# Data_Logger_V3_1.net
KiCad netlist of a schematic drawn in EAGLE
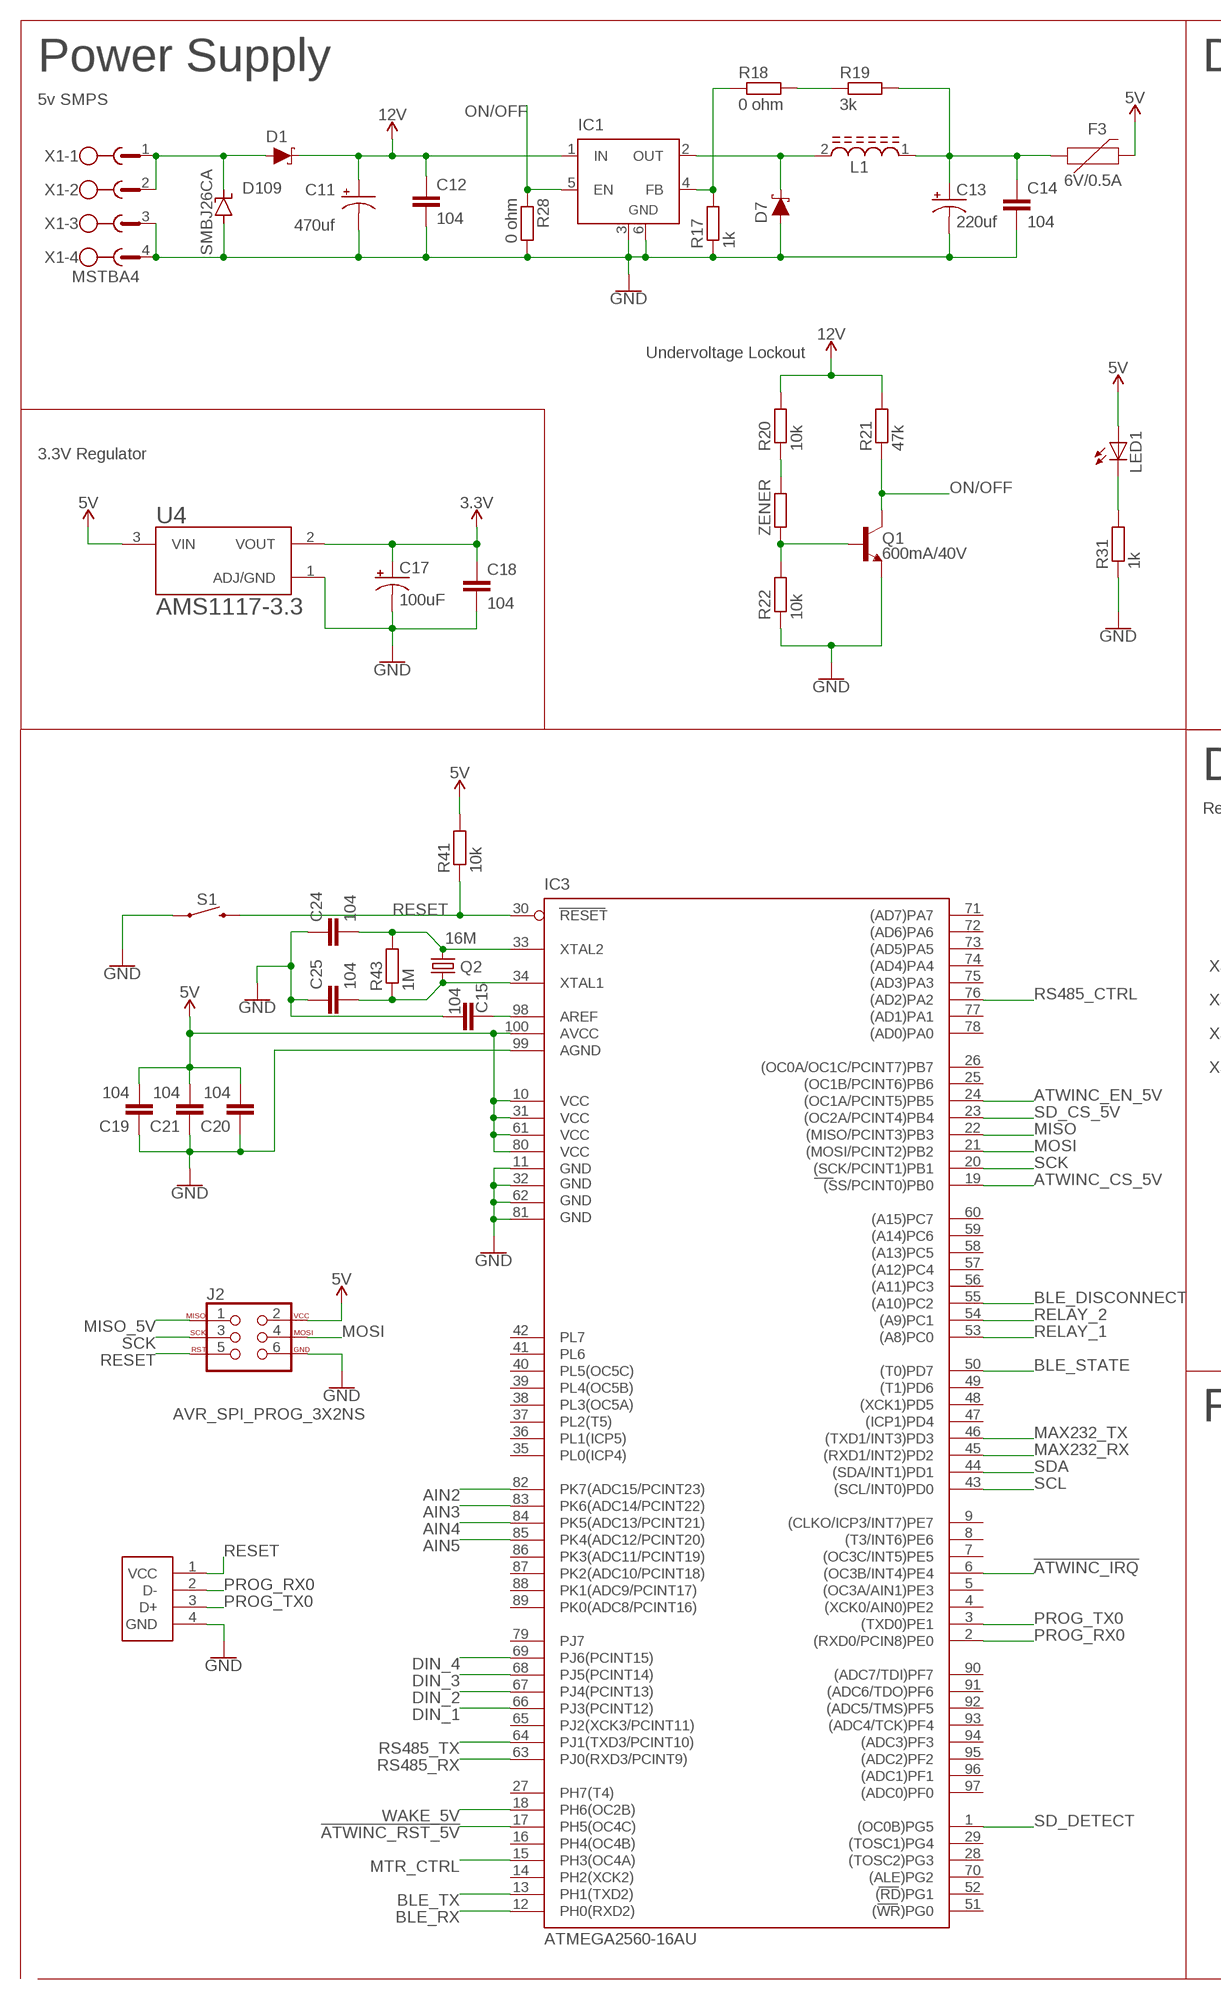
[diagram p0: schematic, sheet 1, part 1 of 3]
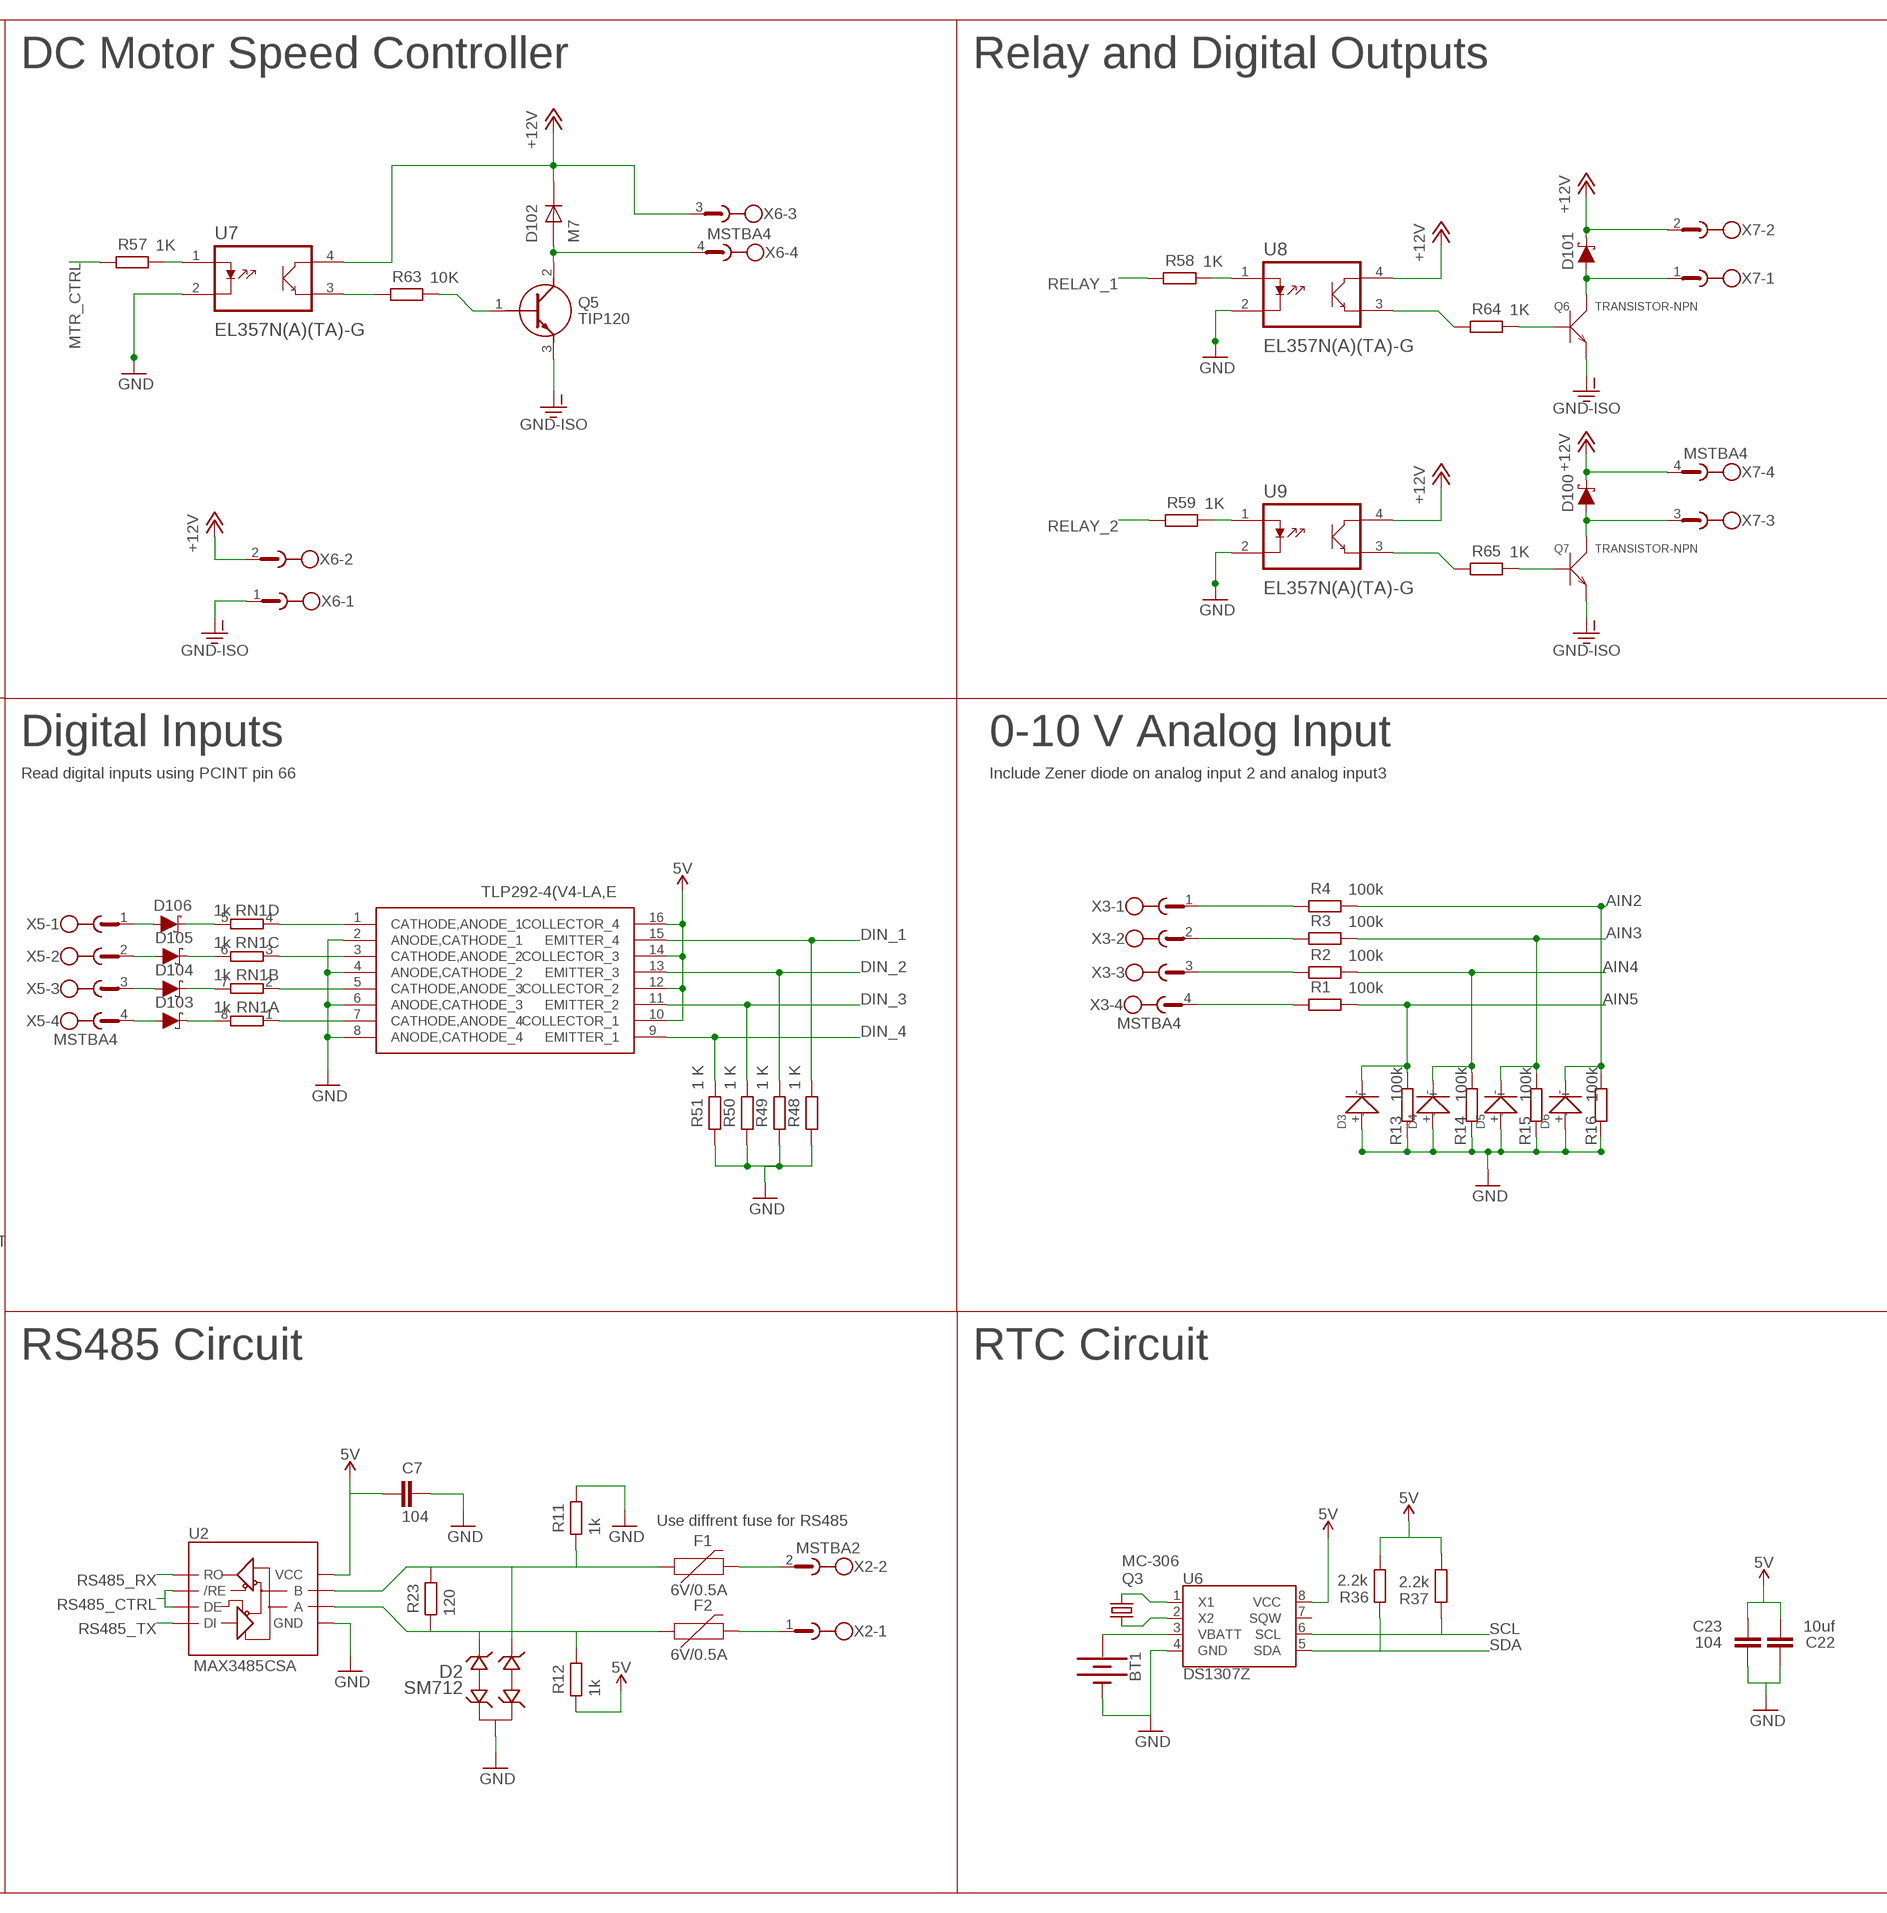
[diagram p1: schematic, sheet 1, part 2 of 3]
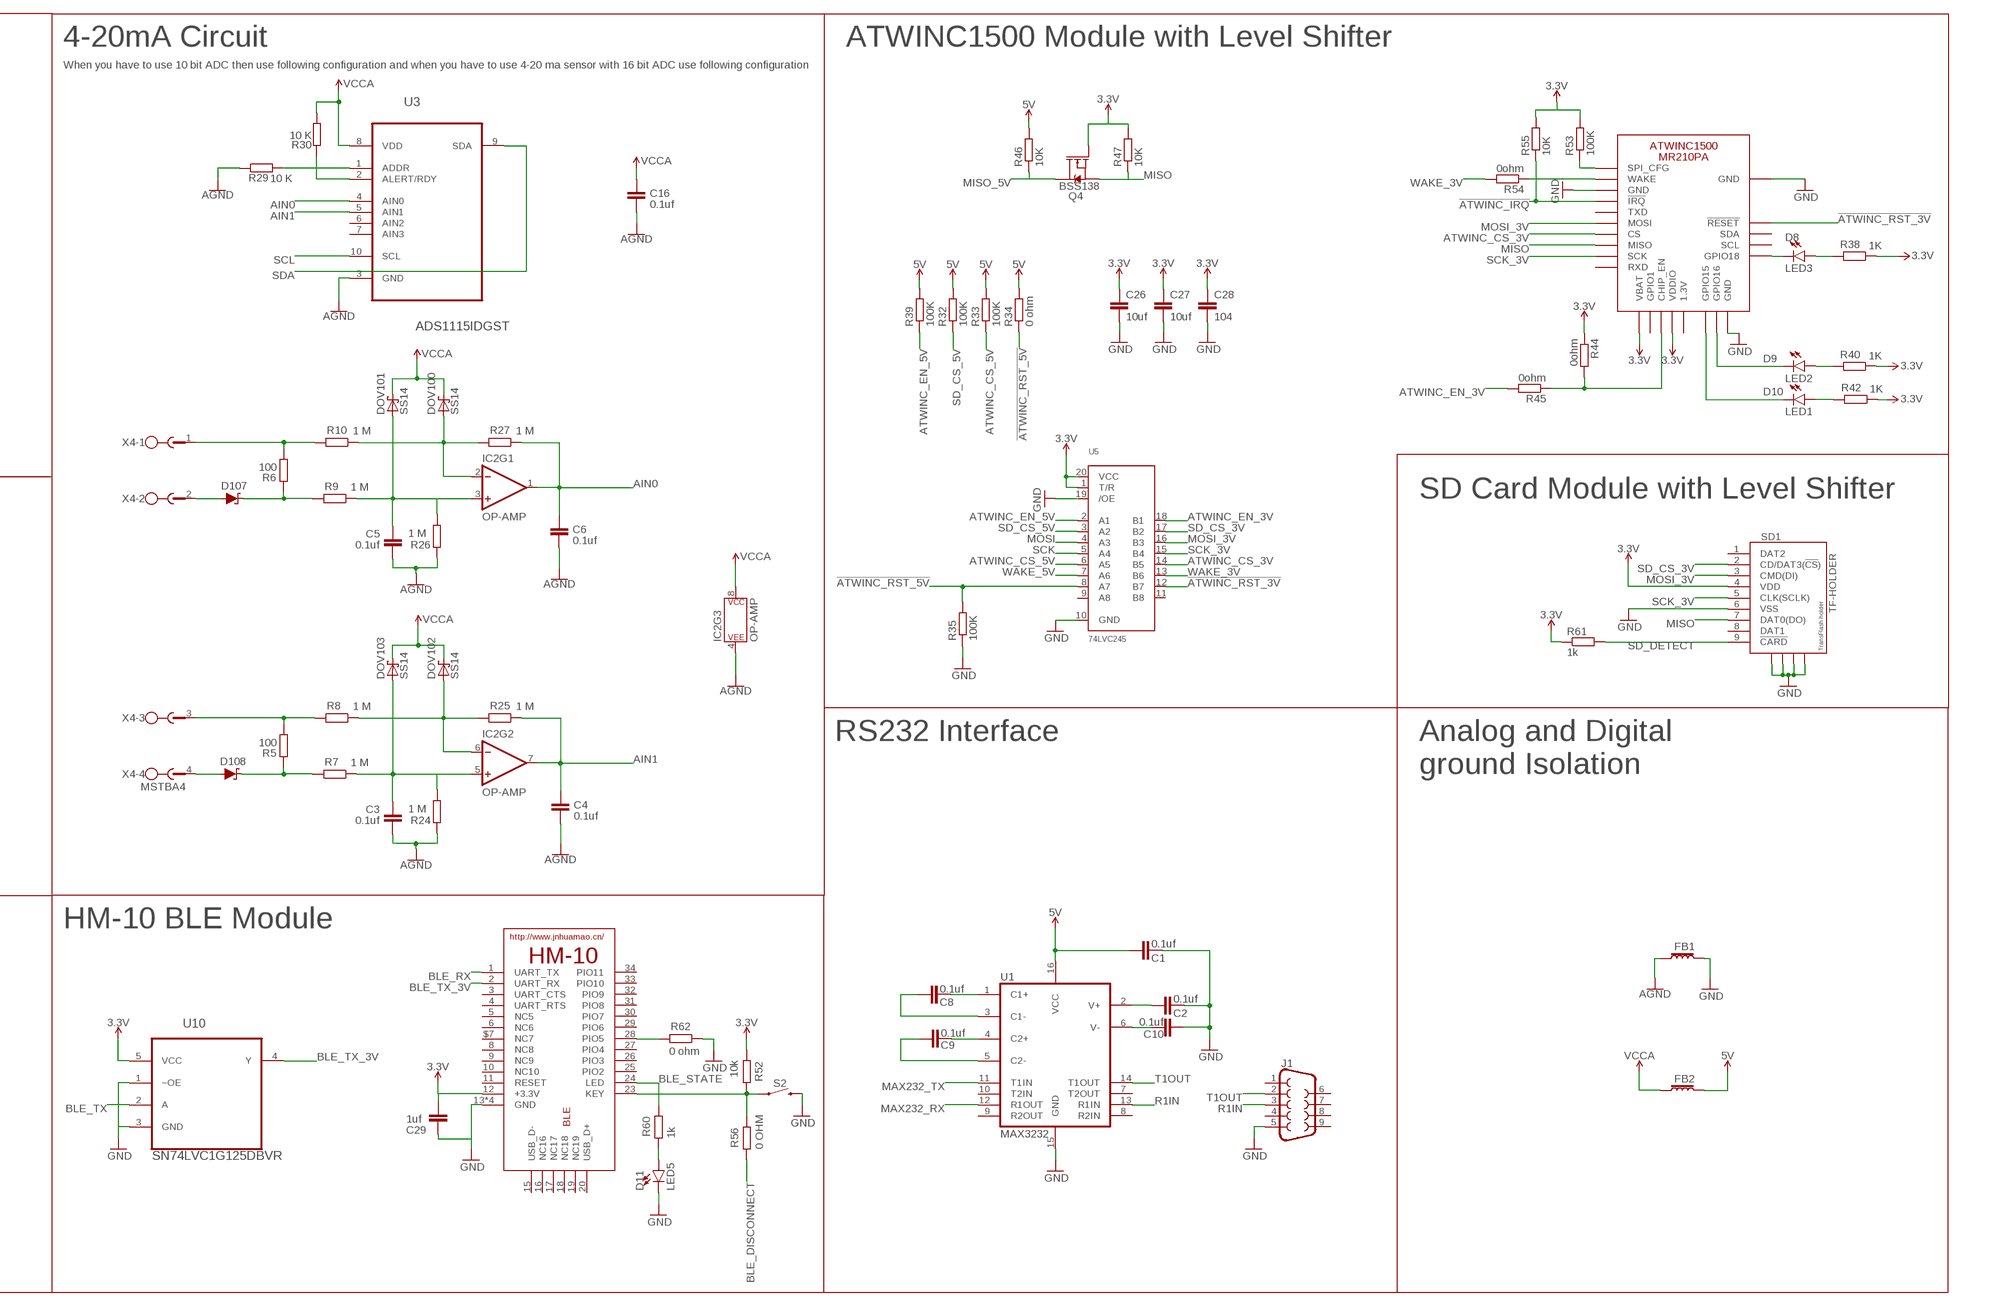
[diagram p2: schematic, sheet 1, part 3 of 3]

(export (version "E")
  (design (tool "Eeschema 10.0.6"))
  (components
    (comp (ref "BLE")
      (value "HM-10-BOARD")
      (footprint "eagle-import:26.9X13X2.2_BOARD")
      (libsource (lib "eagle-import") (part "HM-10-BOARD"))
    )
    (comp (ref "BT1")
      (value "BATTERY-20MM_PTH")
      (footprint "eagle-import:BATTCOM_20MM_PTH")
      (libsource (lib "eagle-import") (part "BATTERY-20MM_PTH"))
    )
    (comp (ref "C1")
      (value "0.1uf")
      (footprint "eagle-import:C0805")
      (libsource (lib "eagle-import") (part "C-EUC0805"))
    )
    (comp (ref "C2")
      (value "0.1uf")
      (footprint "eagle-import:C0805")
      (libsource (lib "eagle-import") (part "C-EUC0805"))
    )
    (comp (ref "C3")
      (value "0.1uf")
      (footprint "eagle-import:C0805")
      (libsource (lib "eagle-import") (part "C-EUC0805"))
    )
    (comp (ref "C4")
      (value "0.1uf")
      (footprint "eagle-import:C0805")
      (libsource (lib "eagle-import") (part "C-EUC0805"))
    )
    (comp (ref "C5")
      (value "0.1uf")
      (footprint "eagle-import:C0805")
      (libsource (lib "eagle-import") (part "C-EUC0805"))
    )
    (comp (ref "C6")
      (value "0.1uf")
      (footprint "eagle-import:C0805")
      (libsource (lib "eagle-import") (part "C-EUC0805"))
    )
    (comp (ref "C7")
      (value "104")
      (footprint "eagle-import:C0805")
      (libsource (lib "eagle-import") (part "C-EUC0805"))
    )
    (comp (ref "C8")
      (value "0.1uf")
      (footprint "eagle-import:C0805")
      (libsource (lib "eagle-import") (part "C-EUC0805"))
    )
    (comp (ref "C9")
      (value "0.1uf")
      (footprint "eagle-import:C0805")
      (libsource (lib "eagle-import") (part "C-EUC0805"))
    )
    (comp (ref "C10")
      (value "0.1uf")
      (footprint "eagle-import:C0805")
      (libsource (lib "eagle-import") (part "C-EUC0805"))
    )
    (comp (ref "C11")
      (value "470uf")
      (footprint "eagle-import:E5-8,5")
      (libsource (lib "eagle-import") (part "CPOL-USE5-8.5"))
    )
    (comp (ref "C12")
      (value "104")
      (footprint "eagle-import:C0805")
      (libsource (lib "eagle-import") (part "C-EUC0805"))
    )
    (comp (ref "C13")
      (value "220uf")
      (footprint "eagle-import:150CLZ-1014")
      (libsource (lib "eagle-import") (part "CPOL-US150CLZ-1014"))
    )
    (comp (ref "C14")
      (value "104")
      (footprint "eagle-import:C0805")
      (libsource (lib "eagle-import") (part "C-EUC0805"))
    )
    (comp (ref "C15")
      (value "104")
      (footprint "eagle-import:C0805")
      (libsource (lib "eagle-import") (part "C-EUC0805"))
    )
    (comp (ref "C16")
      (value "0.1uf")
      (footprint "eagle-import:C0805")
      (libsource (lib "eagle-import") (part "C-EUC0805"))
    )
    (comp (ref "C17")
      (value "100uF")
      (footprint "eagle-import:PANASONIC_D")
      (libsource (lib "eagle-import") (part "100UF-POLAR-25V-20%(ELEC)"))
    )
    (comp (ref "C18")
      (value "104")
      (footprint "eagle-import:C0805")
      (libsource (lib "eagle-import") (part "C-EUC0805"))
    )
    (comp (ref "C19")
      (value "104")
      (footprint "eagle-import:C0805")
      (libsource (lib "eagle-import") (part "C-EUC0805"))
    )
    (comp (ref "C20")
      (value "104")
      (footprint "eagle-import:C0805")
      (libsource (lib "eagle-import") (part "C-EUC0805"))
    )
    (comp (ref "C21")
      (value "104")
      (footprint "eagle-import:C0805")
      (libsource (lib "eagle-import") (part "C-EUC0805"))
    )
    (comp (ref "C22")
      (value "10uf")
      (footprint "eagle-import:C0805")
      (libsource (lib "eagle-import") (part "C-EUC0805"))
    )
    (comp (ref "C23")
      (value "104")
      (footprint "eagle-import:C0805")
      (libsource (lib "eagle-import") (part "C-EUC0805"))
    )
    (comp (ref "C24")
      (value "104")
      (footprint "eagle-import:C0805")
      (libsource (lib "eagle-import") (part "C-EUC0805"))
    )
    (comp (ref "C25")
      (value "104")
      (footprint "eagle-import:C0805")
      (libsource (lib "eagle-import") (part "C-EUC0805"))
    )
    (comp (ref "C26")
      (value "10uf")
      (footprint "eagle-import:C0805")
      (libsource (lib "eagle-import") (part "C-EUC0805"))
    )
    (comp (ref "C27")
      (value "10uf")
      (footprint "eagle-import:C0805")
      (libsource (lib "eagle-import") (part "C-EUC0805"))
    )
    (comp (ref "C28")
      (value "104")
      (footprint "eagle-import:C0805")
      (libsource (lib "eagle-import") (part "C-EUC0805"))
    )
    (comp (ref "C29")
      (value "1uf")
      (footprint "eagle-import:C0805")
      (libsource (lib "eagle-import") (part "C-EUC0805"))
    )
    (comp (ref "D1")
      (value "3A/40V/500mV")
      (footprint "eagle-import:SMA-DIODE")
      (libsource (lib "eagle-import") (part "DIODE-SCHOTTKY-B340A"))
    )
    (comp (ref "D2")
      (value "SM712")
      (footprint "eagle-import:SOT-23-3")
      (fields (field (name "MF") "Bourns") (field (name "MP") "CDSOT23-SM712"))
      (libsource (lib "eagle-import") (part "CDSOT23-SM712"))
    )
    (comp (ref "D3")
      (value "SMD-DIODE-ZENER-5.1V-500MW(SOD-123)")
      (footprint "eagle-import:SOD-123")
      (fields (field (name "MF") "Vishay") (field (name "MP") "MMSZ4689-V-GS08"))
      (libsource (lib "eagle-import") (part "SMD-DIODE-ZENER-5.1V-500MW(SOD-123)"))
    )
    (comp (ref "D4")
      (value "SMD-DIODE-ZENER-5.1V-500MW(SOD-123)")
      (footprint "eagle-import:SOD-123")
      (fields (field (name "MF") "Vishay") (field (name "MP") "MMSZ4689-V-GS08"))
      (libsource (lib "eagle-import") (part "SMD-DIODE-ZENER-5.1V-500MW(SOD-123)"))
    )
    (comp (ref "D5")
      (value "SMD-DIODE-ZENER-5.1V-500MW(SOD-123)")
      (footprint "eagle-import:SOD-123")
      (fields (field (name "MF") "Vishay") (field (name "MP") "MMSZ4689-V-GS08"))
      (libsource (lib "eagle-import") (part "SMD-DIODE-ZENER-5.1V-500MW(SOD-123)"))
    )
    (comp (ref "D6")
      (value "SMD-DIODE-ZENER-5.1V-500MW(SOD-123)")
      (footprint "eagle-import:SOD-123")
      (fields (field (name "MF") "Vishay") (field (name "MP") "MMSZ4689-V-GS08"))
      (libsource (lib "eagle-import") (part "SMD-DIODE-ZENER-5.1V-500MW(SOD-123)"))
    )
    (comp (ref "D7")
      (value "3A/40V/500mV")
      (footprint "eagle-import:SMA-DIODE")
      (libsource (lib "eagle-import") (part "DIODE-SCHOTTKY-B340A"))
    )
    (comp (ref "D8")
      (value "LED3")
      (footprint "eagle-import:LED-0603")
      (libsource (lib "eagle-import") (part "LED-RED0603-SMART"))
    )
    (comp (ref "D9")
      (value "LED2")
      (footprint "eagle-import:LED-0603")
      (libsource (lib "eagle-import") (part "LED-GREEN0603"))
    )
    (comp (ref "D10")
      (value "LED1")
      (footprint "eagle-import:LED-0603")
      (libsource (lib "eagle-import") (part "LED-GREEN0603"))
    )
    (comp (ref "D11")
      (value "LED5")
      (footprint "eagle-import:LED-0603")
      (libsource (lib "eagle-import") (part "LED-GREEN0603"))
    )
    (comp (ref "D100")
      (value "3A/40V/500mV")
      (footprint "eagle-import:SMA-DIODE")
      (libsource (lib "eagle-import") (part "DIODE-SCHOTTKY-B340A"))
    )
    (comp (ref "D101")
      (value "3A/40V/500mV")
      (footprint "eagle-import:SMA-DIODE")
      (libsource (lib "eagle-import") (part "DIODE-SCHOTTKY-B340A"))
    )
    (comp (ref "D102")
      (value "M7")
      (footprint "eagle-import:DIOM505270X240")
      (fields (field (name "MF") "Diodes Inc."))
      (libsource (lib "eagle-import") (part "M7"))
    )
    (comp (ref "D103")
      (value "3A/40V/500mV")
      (footprint "eagle-import:SMA-DIODE")
      (libsource (lib "eagle-import") (part "DIODE-SCHOTTKY-B340A"))
    )
    (comp (ref "D104")
      (value "3A/40V/500mV")
      (footprint "eagle-import:SMA-DIODE")
      (libsource (lib "eagle-import") (part "DIODE-SCHOTTKY-B340A"))
    )
    (comp (ref "D105")
      (value "3A/40V/500mV")
      (footprint "eagle-import:SMA-DIODE")
      (libsource (lib "eagle-import") (part "DIODE-SCHOTTKY-B340A"))
    )
    (comp (ref "D106")
      (value "3A/40V/500mV")
      (footprint "eagle-import:SMA-DIODE")
      (libsource (lib "eagle-import") (part "DIODE-SCHOTTKY-B340A"))
    )
    (comp (ref "D107")
      (value "3A/40V/500mV")
      (footprint "eagle-import:SMA-DIODE")
      (libsource (lib "eagle-import") (part "DIODE-SCHOTTKY-B340A"))
    )
    (comp (ref "D108")
      (value "3A/40V/500mV")
      (footprint "eagle-import:SMA-DIODE")
      (libsource (lib "eagle-import") (part "DIODE-SCHOTTKY-B340A"))
    )
    (comp (ref "D109")
      (value "SMBJ26CA")
      (footprint "eagle-import:SMBJ")
      (libsource (lib "eagle-import") (part "SUPPRESSOR-SMBJ"))
    )
    (comp (ref "DOV100")
      (value "SS14")
      (footprint "eagle-import:DO-214AC")
      (fields (field (name "MF") "ON Semiconductor"))
      (libsource (lib "eagle-import") (part "SS14"))
    )
    (comp (ref "DOV101")
      (value "SS14")
      (footprint "eagle-import:DO-214AC")
      (fields (field (name "MF") "ON Semiconductor"))
      (libsource (lib "eagle-import") (part "SS14"))
    )
    (comp (ref "DOV102")
      (value "SS14")
      (footprint "eagle-import:DO-214AC")
      (fields (field (name "MF") "ON Semiconductor"))
      (libsource (lib "eagle-import") (part "SS14"))
    )
    (comp (ref "DOV103")
      (value "SS14")
      (footprint "eagle-import:DO-214AC")
      (fields (field (name "MF") "ON Semiconductor"))
      (libsource (lib "eagle-import") (part "SS14"))
    )
    (comp (ref "F1")
      (value "6V/0.5A")
      (footprint "eagle-import:1206")
      (libsource (lib "eagle-import") (part "PPTC_HALF-AMP"))
    )
    (comp (ref "F2")
      (value "6V/0.5A")
      (footprint "eagle-import:1206")
      (libsource (lib "eagle-import") (part "PPTC_HALF-AMP"))
    )
    (comp (ref "F3")
      (value "6V/0.5A")
      (footprint "eagle-import:1206")
      (libsource (lib "eagle-import") (part "PPTC_HALF-AMP"))
    )
    (comp (ref "FB1")
      (value "30Ω/1.8A")
      (footprint "eagle-import:0603")
      (libsource (lib "eagle-import") (part "FERRITE_BEAD-0603"))
    )
    (comp (ref "FB2")
      (value "30Ω/1.8A")
      (footprint "eagle-import:0603")
      (libsource (lib "eagle-import") (part "FERRITE_BEAD-0603"))
    )
    (comp (ref "IC1")
      (value "LM2596S")
      (footprint "eagle-import:TO263-5")
      (libsource (lib "eagle-import") (part "LM2596S"))
    )
    (comp (ref "IC2")
      (value "OP-AMP")
      (footprint "eagle-import:SO08")
      (libsource (lib "eagle-import") (part "OPAMP-DUALU"))
    )
    (comp (ref "IC3")
      (value "ATMEGA2560-16AU")
      (footprint "eagle-import:TQFP100")
      (libsource (lib "eagle-import") (part "ATMEGA2560AU2560-16"))
    )
    (comp (ref "IC4")
      (value "TLP292-4(V4-LA,E")
      (footprint "eagle-import:SOIC127P700X230-16N")
      (fields (field (name "MOUSER_PART_NUMBER") "757-TLP292-4V4-LAE"))
      (libsource (lib "eagle-import") (part "TLP292-4(V4-LA,E"))
    )
    (comp (ref "J1")
      (value "DB9MALE")
      (footprint "eagle-import:DB9_MALE")
      (libsource (lib "eagle-import") (part "DB9MALE"))
    )
    (comp (ref "J2")
      (value "AVR_SPI_PROG_3X2NS")
      (footprint "eagle-import:2X3-NS")
      (libsource (lib "eagle-import") (part "AVR_SPI_PROG_3X2NS"))
    )
    (comp (ref "L1")
      (value "SRR1260-680M")
      (footprint "eagle-import:INDP125125X600N")
      (fields (field (name "MF") "Bourns - J.W. Miller"))
      (libsource (lib "eagle-import") (part "SRR1260-680M"))
    )
    (comp (ref "LED1")
      (value "LEDCHIP-LED0805")
      (footprint "eagle-import:CHIP-LED0805")
      (libsource (lib "eagle-import") (part "LEDCHIP-LED0805"))
    )
    (comp (ref "PROG")
      (value "61400416121")
      (footprint "eagle-import:61400416121")
      (libsource (lib "eagle-import") (part "61400416121"))
    )
    (comp (ref "Q1")
      (value "600mA/40V")
      (footprint "eagle-import:SOT23-3")
      (libsource (lib "eagle-import") (part "TRANS_NPN-MMBT2222AL"))
    )
    (comp (ref "Q2")
      (value "16M")
      (footprint "eagle-import:HC49US")
      (libsource (lib "eagle-import") (part "CRYSTALHC49US"))
    )
    (comp (ref "Q3")
      (value "MC-306")
      (footprint "eagle-import:MC-306")
      (fields (field (name "MPN") "MC-306 60.0KHZ  100PPM ,12.5PF"))
      (libsource (lib "eagle-import") (part "MC-306"))
    )
    (comp (ref "Q4")
      (value "BSS138")
      (footprint "eagle-import:SOT23-3")
      (libsource (lib "eagle-import") (part "MOSFET-NCH-AO3404A"))
    )
    (comp (ref "Q5")
      (value "TIP120")
      (footprint "eagle-import:TO220")
      (fields (field (name "MOUSER_PART_NUMBER") "512-TIP120"))
      (libsource (lib "eagle-import") (part "TIP120"))
    )
    (comp (ref "Q6")
      (value "TRANSISTOR-NPN")
      (footprint "eagle-import:SOT-23")
      (fields (field (name "MF") "STMicroelectronics") (field (name "MP") "BC817-40"))
      (libsource (lib "eagle-import") (part "TRANSISTOR-NPN"))
    )
    (comp (ref "Q7")
      (value "TRANSISTOR-NPN")
      (footprint "eagle-import:SOT-23")
      (fields (field (name "MF") "STMicroelectronics") (field (name "MP") "BC817-40"))
      (libsource (lib "eagle-import") (part "TRANSISTOR-NPN"))
    )
    (comp (ref "R1")
      (value "100k")
      (footprint "eagle-import:R0805")
      (libsource (lib "eagle-import") (part "resistor_348_R-EU_R0805"))
    )
    (comp (ref "R2")
      (value "100k")
      (footprint "eagle-import:R0805")
      (libsource (lib "eagle-import") (part "resistor_348_R-EU_R0805"))
    )
    (comp (ref "R3")
      (value "100k")
      (footprint "eagle-import:R0805")
      (libsource (lib "eagle-import") (part "resistor_348_R-EU_R0805"))
    )
    (comp (ref "R4")
      (value "100k")
      (footprint "eagle-import:R0805")
      (libsource (lib "eagle-import") (part "resistor_348_R-EU_R0805"))
    )
    (comp (ref "R5")
      (value "100")
      (footprint "eagle-import:R0805")
      (libsource (lib "eagle-import") (part "resistor_348_R-EU_R0805"))
    )
    (comp (ref "R6")
      (value "100")
      (footprint "eagle-import:R0805")
      (libsource (lib "eagle-import") (part "resistor_348_R-EU_R0805"))
    )
    (comp (ref "R7")
      (value "1 M")
      (footprint "eagle-import:R0805")
      (libsource (lib "eagle-import") (part "resistor_348_R-EU_R0805"))
    )
    (comp (ref "R8")
      (value "1 M")
      (footprint "eagle-import:R0805")
      (libsource (lib "eagle-import") (part "resistor_348_R-EU_R0805"))
    )
    (comp (ref "R9")
      (value "1 M")
      (footprint "eagle-import:R0805")
      (libsource (lib "eagle-import") (part "resistor_348_R-EU_R0805"))
    )
    (comp (ref "R10")
      (value "1 M")
      (footprint "eagle-import:R0805")
      (libsource (lib "eagle-import") (part "resistor_348_R-EU_R0805"))
    )
    (comp (ref "R11")
      (value "1k")
      (footprint "eagle-import:R0805")
      (libsource (lib "eagle-import") (part "resistor_348_R-EU_R0805"))
    )
    (comp (ref "R12")
      (value "1k")
      (footprint "eagle-import:R0805")
      (libsource (lib "eagle-import") (part "resistor_348_R-EU_R0805"))
    )
    (comp (ref "R13")
      (value "100k")
      (footprint "eagle-import:R0805")
      (libsource (lib "eagle-import") (part "resistor_348_R-EU_R0805"))
    )
    (comp (ref "R14")
      (value "100k")
      (footprint "eagle-import:R0805")
      (libsource (lib "eagle-import") (part "resistor_348_R-EU_R0805"))
    )
    (comp (ref "R15")
      (value "100k")
      (footprint "eagle-import:R0805")
      (libsource (lib "eagle-import") (part "resistor_348_R-EU_R0805"))
    )
    (comp (ref "R16")
      (value "100k")
      (footprint "eagle-import:R0805")
      (libsource (lib "eagle-import") (part "resistor_348_R-EU_R0805"))
    )
    (comp (ref "R17")
      (value "1k")
      (footprint "eagle-import:R0805")
      (libsource (lib "eagle-import") (part "R-EU_R0805"))
    )
    (comp (ref "R18")
      (value "0 ohm")
      (footprint "eagle-import:R0805")
      (libsource (lib "eagle-import") (part "R-EU_R0805"))
    )
    (comp (ref "R19")
      (value "3k")
      (footprint "eagle-import:R0805")
      (libsource (lib "eagle-import") (part "R-EU_R0805"))
    )
    (comp (ref "R20")
      (value "10k")
      (footprint "eagle-import:R0805")
      (libsource (lib "eagle-import") (part "R-EU_R0805"))
    )
    (comp (ref "R21")
      (value "47k")
      (footprint "eagle-import:R0805")
      (libsource (lib "eagle-import") (part "R-EU_R0805"))
    )
    (comp (ref "R22")
      (value "10k")
      (footprint "eagle-import:R0805")
      (libsource (lib "eagle-import") (part "R-EU_R0805"))
    )
    (comp (ref "R23")
      (value "120")
      (footprint "eagle-import:R0805")
      (libsource (lib "eagle-import") (part "resistor_348_R-EU_R0805"))
    )
    (comp (ref "R24")
      (value "1 M")
      (footprint "eagle-import:R0805")
      (libsource (lib "eagle-import") (part "resistor_348_R-EU_R0805"))
    )
    (comp (ref "R25")
      (value "1 M")
      (footprint "eagle-import:R0805")
      (libsource (lib "eagle-import") (part "resistor_348_R-EU_R0805"))
    )
    (comp (ref "R26")
      (value "1 M")
      (footprint "eagle-import:R0805")
      (libsource (lib "eagle-import") (part "resistor_348_R-EU_R0805"))
    )
    (comp (ref "R27")
      (value "1 M")
      (footprint "eagle-import:R0805")
      (libsource (lib "eagle-import") (part "resistor_348_R-EU_R0805"))
    )
    (comp (ref "R28")
      (value "0 ohm")
      (footprint "eagle-import:R0805")
      (libsource (lib "eagle-import") (part "R-EU_R0805"))
    )
    (comp (ref "R29")
      (value "10 K")
      (footprint "eagle-import:R0805")
      (libsource (lib "eagle-import") (part "resistor_348_R-EU_R0805"))
    )
    (comp (ref "R30")
      (value "10 K")
      (footprint "eagle-import:R0805")
      (libsource (lib "eagle-import") (part "resistor_348_R-EU_R0805"))
    )
    (comp (ref "R31")
      (value "1k")
      (footprint "eagle-import:R0805")
      (libsource (lib "eagle-import") (part "R-EU_R0805"))
    )
    (comp (ref "R32")
      (value "100K")
      (footprint "eagle-import:R0805")
      (libsource (lib "eagle-import") (part "R-EU_R0805"))
    )
    (comp (ref "R33")
      (value "100K")
      (footprint "eagle-import:R0805")
      (libsource (lib "eagle-import") (part "R-EU_R0805"))
    )
    (comp (ref "R34")
      (value "0 ohm")
      (footprint "eagle-import:R0805")
      (libsource (lib "eagle-import") (part "R-EU_R0805"))
    )
    (comp (ref "R35")
      (value "100K")
      (footprint "eagle-import:R0805")
      (libsource (lib "eagle-import") (part "R-EU_R0805"))
    )
    (comp (ref "R36")
      (value "2.2k")
      (footprint "eagle-import:R0805")
      (libsource (lib "eagle-import") (part "resistor_348_R-EU_R0805"))
    )
    (comp (ref "R37")
      (value "2.2k")
      (footprint "eagle-import:R0805")
      (libsource (lib "eagle-import") (part "resistor_348_R-EU_R0805"))
    )
    (comp (ref "R38")
      (value "1K")
      (footprint "eagle-import:R0805")
      (libsource (lib "eagle-import") (part "R-EU_R0805"))
    )
    (comp (ref "R39")
      (value "100K")
      (footprint "eagle-import:R0805")
      (libsource (lib "eagle-import") (part "R-EU_R0805"))
    )
    (comp (ref "R40")
      (value "1K")
      (footprint "eagle-import:R0805")
      (libsource (lib "eagle-import") (part "R-EU_R0805"))
    )
    (comp (ref "R41")
      (value "10k")
      (footprint "eagle-import:R0805")
      (libsource (lib "eagle-import") (part "R-EU_R0805"))
    )
    (comp (ref "R42")
      (value "1K")
      (footprint "eagle-import:R0805")
      (libsource (lib "eagle-import") (part "R-EU_R0805"))
    )
    (comp (ref "R43")
      (value "1M")
      (footprint "eagle-import:R0805")
      (libsource (lib "eagle-import") (part "R-EU_R0805"))
    )
    (comp (ref "R44")
      (value "0ohm")
      (footprint "eagle-import:R0805")
      (libsource (lib "eagle-import") (part "R-EU_R0805"))
    )
    (comp (ref "R45")
      (value "0ohm")
      (footprint "eagle-import:R0805")
      (libsource (lib "eagle-import") (part "R-EU_R0805"))
    )
    (comp (ref "R46")
      (value "10K")
      (footprint "eagle-import:R0805")
      (libsource (lib "eagle-import") (part "R-EU_R0805"))
    )
    (comp (ref "R47")
      (value "10K")
      (footprint "eagle-import:R0805")
      (libsource (lib "eagle-import") (part "R-EU_R0805"))
    )
    (comp (ref "R48")
      (value "1 K")
      (footprint "eagle-import:R0805")
      (libsource (lib "eagle-import") (part "resistor_348_R-EU_R0805"))
    )
    (comp (ref "R49")
      (value "1 K")
      (footprint "eagle-import:R0805")
      (libsource (lib "eagle-import") (part "resistor_348_R-EU_R0805"))
    )
    (comp (ref "R50")
      (value "1 K")
      (footprint "eagle-import:R0805")
      (libsource (lib "eagle-import") (part "resistor_348_R-EU_R0805"))
    )
    (comp (ref "R51")
      (value "1 K")
      (footprint "eagle-import:R0805")
      (libsource (lib "eagle-import") (part "resistor_348_R-EU_R0805"))
    )
    (comp (ref "R52")
      (value "10k")
      (footprint "eagle-import:R0805")
      (libsource (lib "eagle-import") (part "resistor_348_R-EU_R0805"))
    )
    (comp (ref "R53")
      (value "100K")
      (footprint "eagle-import:R0805")
      (libsource (lib "eagle-import") (part "R-EU_R0805"))
    )
    (comp (ref "R54")
      (value "0ohm")
      (footprint "eagle-import:R0805")
      (libsource (lib "eagle-import") (part "R-EU_R0805"))
    )
    (comp (ref "R55")
      (value "10K")
      (footprint "eagle-import:R0805")
      (libsource (lib "eagle-import") (part "R-EU_R0805"))
    )
    (comp (ref "R56")
      (value "0 OHM")
      (footprint "eagle-import:R0805")
      (libsource (lib "eagle-import") (part "resistor_348_R-EU_R0805"))
    )
    (comp (ref "R57")
      (value "1K")
      (footprint "eagle-import:R0805")
      (libsource (lib "eagle-import") (part "resistor_348_R-EU_R0805"))
    )
    (comp (ref "R58")
      (value "1K")
      (footprint "eagle-import:R0805")
      (libsource (lib "eagle-import") (part "resistor_348_R-EU_R0805"))
    )
    (comp (ref "R59")
      (value "1K")
      (footprint "eagle-import:R0805")
      (libsource (lib "eagle-import") (part "resistor_348_R-EU_R0805"))
    )
    (comp (ref "R60")
      (value "1k")
      (footprint "eagle-import:R0805")
      (libsource (lib "eagle-import") (part "resistor_348_R-EU_R0805"))
    )
    (comp (ref "R61")
      (value "1k")
      (footprint "eagle-import:R0805")
      (libsource (lib "eagle-import") (part "R-EU_R0805"))
    )
    (comp (ref "R62")
      (value "0 ohm")
      (footprint "eagle-import:R0805")
      (libsource (lib "eagle-import") (part "resistor_348_R-EU_R0805"))
    )
    (comp (ref "R63")
      (value "10K")
      (footprint "eagle-import:R0805")
      (libsource (lib "eagle-import") (part "resistor_348_R-EU_R0805"))
    )
    (comp (ref "R64")
      (value "1K")
      (footprint "eagle-import:R0805")
      (libsource (lib "eagle-import") (part "resistor_348_R-EU_R0805"))
    )
    (comp (ref "R65")
      (value "1K")
      (footprint "eagle-import:R0805")
      (libsource (lib "eagle-import") (part "resistor_348_R-EU_R0805"))
    )
    (comp (ref "RN1")
      (value "1k")
      (footprint "eagle-import:CAY16")
      (libsource (lib "eagle-import") (part "4R-NCAY16"))
    )
    (comp (ref "S1")
      (value "MOMENTARY-SWITCH-SPST-SMD-6.0X3.5MM")
      (footprint "eagle-import:TACTILE_SWITCH_SMD_6.0X3.5MM")
      (libsource (lib "eagle-import") (part "MOMENTARY-SWITCH-SPST-SMD-6.0X3.5MM"))
    )
    (comp (ref "S2")
      (value "MOMENTARY-SWITCH-SPST-SMD-6.0X3.5MM")
      (footprint "eagle-import:TACTILE_SWITCH_SMD_6.0X3.5MM")
      (libsource (lib "eagle-import") (part "MOMENTARY-SWITCH-SPST-SMD-6.0X3.5MM"))
    )
    (comp (ref "SD1")
      (value "TF-HOLDER")
      (footprint "eagle-import:TF-PULL")
      (libsource (lib "eagle-import") (part "TF-HOLDER"))
    )
    (comp (ref "U1")
      (value "MAX3232")
      (footprint "eagle-import:SO16")
      (libsource (lib "eagle-import") (part "MAX2323SOIC16"))
    )
    (comp (ref "U2")
      (value "MAX3485CSA")
      (footprint "eagle-import:SO08")
      (libsource (lib "eagle-import") (part "RS485SOIC"))
    )
    (comp (ref "U3")
      (value "ADS1115IDGST")
      (footprint "eagle-import:SOP50P490X110-10N")
      (fields (field (name "MF") "Texas Instruments"))
      (libsource (lib "eagle-import") (part "ADS1115IDGST"))
    )
    (comp (ref "U4")
      (value "AMS1117-3.3")
      (footprint "eagle-import:SOT229P700X180-4N")
      (fields (field (name "MF") "Advanced Monolithic Systems"))
      (libsource (lib "eagle-import") (part "AMS1117-3.3"))
    )
    (comp (ref "U5")
      (value "74LVC245")
      (footprint "eagle-import:TSSOP20")
      (libsource (lib "eagle-import") (part "74LCX245"))
    )
    (comp (ref "U6")
      (value "DS1307Z")
      (footprint "eagle-import:SO08-0.15")
      (libsource (lib "eagle-import") (part "DS1307Z"))
    )
    (comp (ref "U7")
      (value "EL357N(A)(TA)-G")
      (footprint "eagle-import:SOP254P700X200-4N")
      (fields (field (name "MF") "Everlight") (field (name "MP") "EL357N_A__TA_-G"))
      (libsource (lib "eagle-import") (part "EL357N(A)(TA)-G"))
    )
    (comp (ref "U8")
      (value "EL357N(A)(TA)-G")
      (footprint "eagle-import:SOP254P700X200-4N")
      (fields (field (name "MF") "Everlight") (field (name "MP") "EL357N_A__TA_-G"))
      (libsource (lib "eagle-import") (part "EL357N(A)(TA)-G"))
    )
    (comp (ref "U9")
      (value "EL357N(A)(TA)-G")
      (footprint "eagle-import:SOP254P700X200-4N")
      (fields (field (name "MF") "Everlight") (field (name "MP") "EL357N_A__TA_-G"))
      (libsource (lib "eagle-import") (part "EL357N(A)(TA)-G"))
    )
    (comp (ref "U10")
      (value "SN74LVC1G125DBVR")
      (footprint "eagle-import:SOT95P280X145-5N")
      (fields (field (name "MF") "Texas Instruments"))
      (libsource (lib "eagle-import") (part "SN74LVC1G125DBVR"))
    )
    (comp (ref "WIFI")
      (value "ATWINC1500_MR210PB")
      (footprint "eagle-import:ATWINC1500_MR210PA")
      (libsource (lib "eagle-import") (part "ATWINC1500_MR210PA"))
    )
    (comp (ref "X1")
      (value "MSTBA4")
      (footprint "eagle-import:MSTBA4")
      (fields (field (name "MF") "FARNELL") (field (name "MPN") "1757268"))
      (libsource (lib "eagle-import") (part "MSTBA4"))
    )
    (comp (ref "X2")
      (value "MSTBA2")
      (footprint "eagle-import:MSTBA2")
      (fields (field (name "MF") "FARNELL") (field (name "MPN") "1757242"))
      (libsource (lib "eagle-import") (part "MSTBA2"))
    )
    (comp (ref "X3")
      (value "MSTBA4")
      (footprint "eagle-import:MSTBA4")
      (fields (field (name "MF") "FARNELL") (field (name "MPN") "1757268"))
      (libsource (lib "eagle-import") (part "MSTBA4"))
    )
    (comp (ref "X4")
      (value "MSTBA4")
      (footprint "eagle-import:MSTBA4")
      (fields (field (name "MF") "FARNELL") (field (name "MPN") "1757268"))
      (libsource (lib "eagle-import") (part "MSTBA4"))
    )
    (comp (ref "X5")
      (value "MSTBA4")
      (footprint "eagle-import:MSTBA4")
      (fields (field (name "MF") "FARNELL") (field (name "MPN") "1757268"))
      (libsource (lib "eagle-import") (part "MSTBA4"))
    )
    (comp (ref "X6")
      (value "MSTBA4")
      (footprint "eagle-import:MSTBA4")
      (fields (field (name "MF") "FARNELL") (field (name "MPN") "1757268"))
      (libsource (lib "eagle-import") (part "MSTBA4"))
    )
    (comp (ref "X7")
      (value "MSTBA4")
      (footprint "eagle-import:MSTBA4")
      (fields (field (name "MF") "FARNELL") (field (name "MPN") "1757268"))
      (libsource (lib "eagle-import") (part "MSTBA4"))
    )
    (comp (ref "ZENER")
      (value "R0204/7")
      (footprint "eagle-import:0204_7")
      (libsource (lib "eagle-import") (part "R0204/7"))
    )
  )
  (nets
    (net (code "1") (name "+12V") (class "Default")
      (node (ref "D100") (pin "C") (pinfunction "C_C") (pintype "passive"))
      (node (ref "D101") (pin "C") (pinfunction "C_C") (pintype "passive"))
      (node (ref "D102") (pin "C") (pinfunction "C_C") (pintype "passive"))
      (node (ref "U7") (pin "4") (pinfunction "C_4") (pintype "passive"))
      (node (ref "U8") (pin "4") (pinfunction "C_4") (pintype "passive"))
      (node (ref "U9") (pin "4") (pinfunction "C_4") (pintype "passive"))
      (node (ref "X6") (pin "2") (pinfunction "1_2") (pintype "passive"))
      (node (ref "X6") (pin "3") (pinfunction "1_3") (pintype "passive"))
      (node (ref "X7") (pin "2") (pinfunction "1_2") (pintype "passive"))
      (node (ref "X7") (pin "4") (pinfunction "1_4") (pintype "passive"))
    )
    (net (code "2") (name "/AIN0") (class "Default")
      (node (ref "C6") (pin "2") (pinfunction "2_2") (pintype "passive"))
      (node (ref "IC2") (pin "1") (pinfunction "OUT_1") (pintype "output"))
      (node (ref "R27") (pin "1") (pinfunction "1_1") (pintype "passive"))
      (node (ref "U3") (pin "4") (pinfunction "AIN0_4") (pintype "input"))
    )
    (net (code "3") (name "/AIN1") (class "Default")
      (node (ref "C4") (pin "2") (pinfunction "2_2") (pintype "passive"))
      (node (ref "IC2") (pin "7") (pinfunction "OUT_7") (pintype "output"))
      (node (ref "R25") (pin "1") (pinfunction "1_1") (pintype "passive"))
      (node (ref "U3") (pin "5") (pinfunction "AIN1_5") (pintype "input"))
    )
    (net (code "4") (name "/AIN2") (class "Default")
      (node (ref "D6") (pin "-") (pinfunction "-_-") (pintype "passive"))
      (node (ref "IC3") (pin "82") (pinfunction "PK7(ADC15/PCINT23)_82") (pintype "bidirectional"))
      (node (ref "R16") (pin "1") (pinfunction "1_1") (pintype "passive"))
      (node (ref "R4") (pin "1") (pinfunction "1_1") (pintype "passive"))
    )
    (net (code "5") (name "/AIN3") (class "Default")
      (node (ref "D5") (pin "-") (pinfunction "-_-") (pintype "passive"))
      (node (ref "IC3") (pin "83") (pinfunction "PK6(ADC14/PCINT22)_83") (pintype "bidirectional"))
      (node (ref "R15") (pin "1") (pinfunction "1_1") (pintype "passive"))
      (node (ref "R3") (pin "1") (pinfunction "1_1") (pintype "passive"))
    )
    (net (code "6") (name "/AIN4") (class "Default")
      (node (ref "D4") (pin "-") (pinfunction "-_-") (pintype "passive"))
      (node (ref "IC3") (pin "84") (pinfunction "PK5(ADC13/PCINT21)_84") (pintype "bidirectional"))
      (node (ref "R14") (pin "1") (pinfunction "1_1") (pintype "passive"))
      (node (ref "R2") (pin "1") (pinfunction "1_1") (pintype "passive"))
    )
    (net (code "7") (name "/AIN5") (class "Default")
      (node (ref "D3") (pin "-") (pinfunction "-_-") (pintype "passive"))
      (node (ref "IC3") (pin "85") (pinfunction "PK4(ADC12/PCINT20)_85") (pintype "bidirectional"))
      (node (ref "R1") (pin "1") (pinfunction "1_1") (pintype "passive"))
      (node (ref "R13") (pin "1") (pinfunction "1_1") (pintype "passive"))
    )
    (net (code "8") (name "/ATWINC_CS_3V") (class "Default")
      (node (ref "U5") (pin "14") (pinfunction "B5_14") (pintype "bidirectional"))
      (node (ref "WIFI") (pin "J16") (pinfunction "CS_J16") (pintype "input"))
    )
    (net (code "9") (name "/ATWINC_CS_5V") (class "Default")
      (node (ref "IC3") (pin "19") (pinfunction "(SS/PCINT0)PB0_19") (pintype "bidirectional"))
      (node (ref "R33") (pin "1") (pinfunction "1_1") (pintype "passive"))
      (node (ref "U5") (pin "6") (pinfunction "A5_6") (pintype "bidirectional"))
    )
    (net (code "10") (name "/ATWINC_EN_3V") (class "Default")
      (node (ref "R45") (pin "2") (pinfunction "2_2") (pintype "passive"))
      (node (ref "U5") (pin "18") (pinfunction "B1_18") (pintype "bidirectional"))
    )
    (net (code "11") (name "/ATWINC_EN_5V") (class "Default")
      (node (ref "IC3") (pin "24") (pinfunction "(OC1A/PCINT5)PB5_24") (pintype "bidirectional"))
      (node (ref "R39") (pin "1") (pinfunction "1_1") (pintype "passive"))
      (node (ref "U5") (pin "2") (pinfunction "A1_2") (pintype "bidirectional"))
    )
    (net (code "12") (name "/BLE_DISCONNECT") (class "Default")
      (node (ref "IC3") (pin "55") (pinfunction "(A10)PC2_55") (pintype "bidirectional"))
      (node (ref "R56") (pin "2") (pinfunction "2_2") (pintype "passive"))
    )
    (net (code "13") (name "/BLE_RX") (class "Default")
      (node (ref "BLE") (pin "1") (pinfunction "UART_TX_1") (pintype "bidirectional"))
      (node (ref "IC3") (pin "12") (pinfunction "PH0(RXD2)_12") (pintype "bidirectional"))
    )
    (net (code "14") (name "/BLE_STATE") (class "Default")
      (node (ref "BLE") (pin "24") (pinfunction "LED_24") (pintype "bidirectional"))
      (node (ref "IC3") (pin "50") (pinfunction "(T0)PD7_50") (pintype "bidirectional"))
      (node (ref "R60") (pin "1") (pinfunction "1_1") (pintype "passive"))
    )
    (net (code "15") (name "/BLE_TX") (class "Default")
      (node (ref "IC3") (pin "13") (pinfunction "PH1(TXD2)_13") (pintype "bidirectional"))
      (node (ref "U10") (pin "2") (pinfunction "A_2") (pintype "input"))
    )
    (net (code "16") (name "/BLE_TX_3V") (class "Default")
      (node (ref "BLE") (pin "2") (pinfunction "UART_RX_2") (pintype "bidirectional"))
      (node (ref "U10") (pin "4") (pinfunction "Y_4") (pintype "output"))
    )
    (net (code "17") (name "/DIN_1") (class "Default")
      (node (ref "IC3") (pin "66") (pinfunction "PJ3(PCINT12)_66") (pintype "bidirectional"))
      (node (ref "IC4") (pin "15") (pinfunction "EMITTER_4_15") (pintype "bidirectional"))
      (node (ref "R48") (pin "1") (pinfunction "1_1") (pintype "passive"))
    )
    (net (code "18") (name "/DIN_2") (class "Default")
      (node (ref "IC3") (pin "67") (pinfunction "PJ4(PCINT13)_67") (pintype "bidirectional"))
      (node (ref "IC4") (pin "13") (pinfunction "EMITTER_3_13") (pintype "bidirectional"))
      (node (ref "R49") (pin "1") (pinfunction "1_1") (pintype "passive"))
    )
    (net (code "19") (name "/DIN_3") (class "Default")
      (node (ref "IC3") (pin "68") (pinfunction "PJ5(PCINT14)_68") (pintype "bidirectional"))
      (node (ref "IC4") (pin "11") (pinfunction "EMITTER_2_11") (pintype "bidirectional"))
      (node (ref "R50") (pin "1") (pinfunction "1_1") (pintype "passive"))
    )
    (net (code "20") (name "/DIN_4") (class "Default")
      (node (ref "IC3") (pin "69") (pinfunction "PJ6(PCINT15)_69") (pintype "bidirectional"))
      (node (ref "IC4") (pin "9") (pinfunction "EMITTER_1_9") (pintype "bidirectional"))
      (node (ref "R51") (pin "1") (pinfunction "1_1") (pintype "passive"))
    )
    (net (code "21") (name "/MAX232_RX") (class "Default")
      (node (ref "IC3") (pin "45") (pinfunction "(RXD1/INT2)PD2_45") (pintype "bidirectional"))
      (node (ref "U1") (pin "12") (pinfunction "R1OUT_12") (pintype "output"))
    )
    (net (code "22") (name "/MAX232_TX") (class "Default")
      (node (ref "IC3") (pin "46") (pinfunction "(TXD1/INT3)PD3_46") (pintype "bidirectional"))
      (node (ref "U1") (pin "11") (pinfunction "T1IN_11") (pintype "input"))
    )
    (net (code "23") (name "/MISO") (class "Default")
      (node (ref "IC3") (pin "22") (pinfunction "(MISO/PCINT3)PB3_22") (pintype "bidirectional"))
      (node (ref "Q4") (pin "2") (pinfunction "S_2") (pintype "bidirectional"))
      (node (ref "R47") (pin "1") (pinfunction "1_1") (pintype "passive"))
      (node (ref "SD1") (pin "7") (pinfunction "DAT0(DO)_7") (pintype "bidirectional"))
      (node (ref "WIFI") (pin "J17") (pinfunction "MISO_J17") (pintype "output"))
    )
    (net (code "24") (name "/MISO_5V") (class "Default")
      (node (ref "J2") (pin "1") (pinfunction "1_1") (pintype "passive"))
      (node (ref "Q4") (pin "3") (pinfunction "D_3") (pintype "bidirectional"))
      (node (ref "R46") (pin "1") (pinfunction "1_1") (pintype "passive"))
    )
    (net (code "25") (name "/MOSI") (class "Default")
      (node (ref "IC3") (pin "21") (pinfunction "(MOSI/PCINT2)PB2_21") (pintype "bidirectional"))
      (node (ref "J2") (pin "4") (pinfunction "4_4") (pintype "passive"))
      (node (ref "U5") (pin "4") (pinfunction "A3_4") (pintype "bidirectional"))
    )
    (net (code "26") (name "/MOSI_3V") (class "Default")
      (node (ref "SD1") (pin "3") (pinfunction "CMD(DI)_3") (pintype "bidirectional"))
      (node (ref "U5") (pin "16") (pinfunction "B3_16") (pintype "bidirectional"))
      (node (ref "WIFI") (pin "J15") (pinfunction "MOSI_J15") (pintype "input"))
    )
    (net (code "27") (name "/MTR_CTRL") (class "Default")
      (node (ref "IC3") (pin "15") (pinfunction "PH3(OC4A)_15") (pintype "bidirectional"))
      (node (ref "R57") (pin "2") (pinfunction "2_2") (pintype "passive"))
    )
    (net (code "28") (name "/ON{slash}OFF") (class "Default")
      (node (ref "IC1") (pin "5") (pinfunction "EN_5") (pintype "input"))
      (node (ref "Q1") (pin "3") (pinfunction "C_3") (pintype "passive"))
      (node (ref "R21") (pin "1") (pinfunction "1_1") (pintype "passive"))
      (node (ref "R28") (pin "1") (pinfunction "1_1") (pintype "passive"))
    )
    (net (code "29") (name "/PROG_RX0") (class "Default")
      (node (ref "IC3") (pin "2") (pinfunction "(RXD0/PCIN8)PE0_2") (pintype "bidirectional"))
      (node (ref "PROG") (pin "2") (pinfunction "D-_2") (pintype "passive"))
    )
    (net (code "30") (name "/PROG_TX0") (class "Default")
      (node (ref "IC3") (pin "3") (pinfunction "(TXD0)PE1_3") (pintype "bidirectional"))
      (node (ref "PROG") (pin "3") (pinfunction "D+_3") (pintype "passive"))
    )
    (net (code "31") (name "/R1IN") (class "Default")
      (node (ref "J1") (pin "3") (pinfunction "3_3") (pintype "passive"))
      (node (ref "U1") (pin "13") (pinfunction "R1IN_13") (pintype "input"))
    )
    (net (code "32") (name "/RELAY_1") (class "Default")
      (node (ref "IC3") (pin "53") (pinfunction "(A8)PC0_53") (pintype "bidirectional"))
      (node (ref "R58") (pin "2") (pinfunction "2_2") (pintype "passive"))
    )
    (net (code "33") (name "/RELAY_2") (class "Default")
      (node (ref "IC3") (pin "54") (pinfunction "(A9)PC1_54") (pintype "bidirectional"))
      (node (ref "R59") (pin "2") (pinfunction "2_2") (pintype "passive"))
    )
    (net (code "34") (name "/RESET") (class "Default")
      (node (ref "IC3") (pin "30") (pinfunction "RESET_30") (pintype "input"))
      (node (ref "J2") (pin "5") (pinfunction "5_5") (pintype "passive"))
      (node (ref "PROG") (pin "1") (pinfunction "VCC_1") (pintype "passive"))
      (node (ref "R41") (pin "1") (pinfunction "1_1") (pintype "passive"))
      (node (ref "S1") (pin "2") (pinfunction "2_2") (pintype "passive"))
    )
    (net (code "35") (name "/RS485_CTRL") (class "Default")
      (node (ref "IC3") (pin "76") (pinfunction "(AD2)PA2_76") (pintype "bidirectional"))
      (node (ref "U2") (pin "2") (pinfunction "/RE_2") (pintype "bidirectional"))
      (node (ref "U2") (pin "3") (pinfunction "DE_3") (pintype "bidirectional"))
    )
    (net (code "36") (name "/RS485_RX") (class "Default")
      (node (ref "IC3") (pin "63") (pinfunction "PJ0(RXD3/PCINT9)_63") (pintype "bidirectional"))
      (node (ref "U2") (pin "1") (pinfunction "RO_1") (pintype "bidirectional"))
    )
    (net (code "37") (name "/RS485_TX") (class "Default")
      (node (ref "IC3") (pin "64") (pinfunction "PJ1(TXD3/PCINT10)_64") (pintype "bidirectional"))
      (node (ref "U2") (pin "4") (pinfunction "DI_4") (pintype "bidirectional"))
    )
    (net (code "38") (name "/SCK") (class "Default")
      (node (ref "IC3") (pin "20") (pinfunction "(SCK/PCINT1)PB1_20") (pintype "bidirectional"))
      (node (ref "J2") (pin "3") (pinfunction "3_3") (pintype "passive"))
      (node (ref "U5") (pin "5") (pinfunction "A4_5") (pintype "bidirectional"))
    )
    (net (code "39") (name "/SCK_3V") (class "Default")
      (node (ref "SD1") (pin "5") (pinfunction "CLK(SCLK)_5") (pintype "input"))
      (node (ref "U5") (pin "15") (pinfunction "B4_15") (pintype "bidirectional"))
      (node (ref "WIFI") (pin "J18") (pinfunction "SCK_J18") (pintype "input"))
    )
    (net (code "40") (name "/SCL") (class "Default")
      (node (ref "IC3") (pin "43") (pinfunction "(SCL/INT0)PD0_43") (pintype "bidirectional"))
      (node (ref "R37") (pin "2") (pinfunction "2_2") (pintype "passive"))
      (node (ref "U3") (pin "10") (pinfunction "SCL_10") (pintype "input"))
      (node (ref "U6") (pin "6") (pinfunction "SCL_6") (pintype "bidirectional"))
    )
    (net (code "41") (name "/SDA") (class "Default")
      (node (ref "IC3") (pin "44") (pinfunction "(SDA/INT1)PD1_44") (pintype "bidirectional"))
      (node (ref "R36") (pin "2") (pinfunction "2_2") (pintype "passive"))
      (node (ref "U3") (pin "9") (pinfunction "SDA_9") (pintype "bidirectional"))
      (node (ref "U6") (pin "5") (pinfunction "SDA_5") (pintype "bidirectional"))
    )
    (net (code "42") (name "/SD_CS_3V") (class "Default")
      (node (ref "SD1") (pin "2") (pinfunction "CD/DAT3(~{CS})_2") (pintype "bidirectional"))
      (node (ref "U5") (pin "17") (pinfunction "B2_17") (pintype "bidirectional"))
    )
    (net (code "43") (name "/SD_CS_5V") (class "Default")
      (node (ref "IC3") (pin "23") (pinfunction "(OC2A/PCINT4)PB4_23") (pintype "bidirectional"))
      (node (ref "R32") (pin "1") (pinfunction "1_1") (pintype "passive"))
      (node (ref "U5") (pin "3") (pinfunction "A2_3") (pintype "bidirectional"))
    )
    (net (code "44") (name "/SD_DETECT") (class "Default")
      (node (ref "IC3") (pin "1") (pinfunction "(OC0B)PG5_1") (pintype "bidirectional"))
      (node (ref "R61") (pin "2") (pinfunction "2_2") (pintype "passive"))
      (node (ref "SD1") (pin "9") (pinfunction "~{CARD}_9") (pintype "passive"))
    )
    (net (code "45") (name "/T1OUT") (class "Default")
      (node (ref "J1") (pin "2") (pinfunction "2_2") (pintype "passive"))
      (node (ref "U1") (pin "14") (pinfunction "T1OUT_14") (pintype "output"))
    )
    (net (code "46") (name "/WAKE_3V") (class "Default")
      (node (ref "R54") (pin "2") (pinfunction "2_2") (pintype "passive"))
      (node (ref "U5") (pin "13") (pinfunction "B6_13") (pintype "bidirectional"))
    )
    (net (code "47") (name "/WAKE_5V") (class "Default")
      (node (ref "IC3") (pin "18") (pinfunction "PH6(OC2B)_18") (pintype "bidirectional"))
      (node (ref "U5") (pin "7") (pinfunction "A6_7") (pintype "bidirectional"))
    )
    (net (code "48") (name "/~{ATWINC_IRQ}") (class "Default")
      (node (ref "IC3") (pin "6") (pinfunction "(OC3B/INT4)PE4_6") (pintype "bidirectional"))
      (node (ref "R55") (pin "1") (pinfunction "1_1") (pintype "passive"))
      (node (ref "WIFI") (pin "J13") (pinfunction "~{IRQ}_J13") (pintype "output"))
    )
    (net (code "49") (name "/~{ATWINC_RST_3V}") (class "Default")
      (node (ref "U5") (pin "12") (pinfunction "B7_12") (pintype "bidirectional"))
      (node (ref "WIFI") (pin "J4") (pinfunction "~{RESET}_J4") (pintype "input"))
    )
    (net (code "50") (name "/~{ATWINC_RST_5V}") (class "Default")
      (node (ref "IC3") (pin "17") (pinfunction "PH5(OC4C)_17") (pintype "bidirectional"))
      (node (ref "R34") (pin "1") (pinfunction "1_1") (pintype "passive"))
      (node (ref "R35") (pin "2") (pinfunction "2_2") (pintype "passive"))
      (node (ref "U5") (pin "8") (pinfunction "A7_8") (pintype "bidirectional"))
    )
    (net (code "51") (name "3.3V") (class "Default")
      (node (ref "BLE") (pin "12") (pinfunction "+3.3V_12") (pintype "bidirectional"))
      (node (ref "C17") (pin "+") (pinfunction "+_+") (pintype "passive"))
      (node (ref "C18") (pin "1") (pinfunction "1_1") (pintype "passive"))
      (node (ref "C26") (pin "1") (pinfunction "1_1") (pintype "passive"))
      (node (ref "C27") (pin "1") (pinfunction "1_1") (pintype "passive"))
      (node (ref "C28") (pin "1") (pinfunction "1_1") (pintype "passive"))
      (node (ref "C29") (pin "2") (pinfunction "2_2") (pintype "passive"))
      (node (ref "Q4") (pin "1") (pinfunction "G_1") (pintype "bidirectional"))
      (node (ref "R38") (pin "1") (pinfunction "1_1") (pintype "passive"))
      (node (ref "R40") (pin "1") (pinfunction "1_1") (pintype "passive"))
      (node (ref "R42") (pin "1") (pinfunction "1_1") (pintype "passive"))
      (node (ref "R44") (pin "1") (pinfunction "1_1") (pintype "passive"))
      (node (ref "R47") (pin "2") (pinfunction "2_2") (pintype "passive"))
      (node (ref "R52") (pin "2") (pinfunction "2_2") (pintype "passive"))
      (node (ref "R53") (pin "2") (pinfunction "2_2") (pintype "passive"))
      (node (ref "R55") (pin "2") (pinfunction "2_2") (pintype "passive"))
      (node (ref "R61") (pin "1") (pinfunction "1_1") (pintype "passive"))
      (node (ref "SD1") (pin "4") (pinfunction "VDD_4") (pintype "power_in"))
      (node (ref "U10") (pin "5") (pinfunction "VCC_5") (pintype "power_in"))
      (node (ref "U4") (pin "2") (pinfunction "VOUT_2") (pintype "output"))
      (node (ref "U5") (pin "1") (pinfunction "T/R_1") (pintype "bidirectional"))
      (node (ref "U5") (pin "20") (pinfunction "VCC_20") (pintype "bidirectional"))
      (node (ref "WIFI") (pin "J20") (pinfunction "VBAT_J20") (pintype "power_in"))
      (node (ref "WIFI") (pin "J23") (pinfunction "VDDIO_J23") (pintype "power_in"))
    )
    (net (code "52") (name "5V") (class "Default")
      (node (ref "C1") (pin "2") (pinfunction "2_2") (pintype "passive"))
      (node (ref "C19") (pin "2") (pinfunction "2_2") (pintype "passive"))
      (node (ref "C20") (pin "2") (pinfunction "2_2") (pintype "passive"))
      (node (ref "C21") (pin "2") (pinfunction "2_2") (pintype "passive"))
      (node (ref "C22") (pin "2") (pinfunction "2_2") (pintype "passive"))
      (node (ref "C23") (pin "2") (pinfunction "2_2") (pintype "passive"))
      (node (ref "C7") (pin "1") (pinfunction "1_1") (pintype "passive"))
      (node (ref "F3") (pin "2") (pinfunction "2_2") (pintype "bidirectional"))
      (node (ref "FB2") (pin "2") (pinfunction "2_2") (pintype "passive"))
      (node (ref "IC3") (pin "10") (pinfunction "VCC_10") (pintype "power_in"))
      (node (ref "IC3") (pin "100") (pinfunction "AVCC_100") (pintype "power_in"))
      (node (ref "IC3") (pin "31") (pinfunction "VCC1_31") (pintype "power_in"))
      (node (ref "IC3") (pin "61") (pinfunction "VCC2_61") (pintype "power_in"))
      (node (ref "IC3") (pin "80") (pinfunction "VCC3_80") (pintype "power_in"))
      (node (ref "IC4") (pin "10") (pinfunction "COLLECTOR_1_10") (pintype "bidirectional"))
      (node (ref "IC4") (pin "12") (pinfunction "COLLECTOR_2_12") (pintype "bidirectional"))
      (node (ref "IC4") (pin "14") (pinfunction "COLLECTOR_3_14") (pintype "bidirectional"))
      (node (ref "IC4") (pin "16") (pinfunction "COLLECTOR_4_16") (pintype "bidirectional"))
      (node (ref "J2") (pin "2") (pinfunction "2_2") (pintype "passive"))
      (node (ref "LED1") (pin "A") (pinfunction "A_A") (pintype "passive"))
      (node (ref "R12") (pin "2") (pinfunction "2_2") (pintype "passive"))
      (node (ref "R32") (pin "2") (pinfunction "2_2") (pintype "passive"))
      (node (ref "R33") (pin "2") (pinfunction "2_2") (pintype "passive"))
      (node (ref "R34") (pin "2") (pinfunction "2_2") (pintype "passive"))
      (node (ref "R36") (pin "1") (pinfunction "1_1") (pintype "passive"))
      (node (ref "R37") (pin "1") (pinfunction "1_1") (pintype "passive"))
      (node (ref "R39") (pin "2") (pinfunction "2_2") (pintype "passive"))
      (node (ref "R41") (pin "2") (pinfunction "2_2") (pintype "passive"))
      (node (ref "R46") (pin "2") (pinfunction "2_2") (pintype "passive"))
      (node (ref "U1") (pin "16") (pinfunction "VCC_16") (pintype "bidirectional"))
      (node (ref "U2") (pin "8") (pinfunction "VCC_8") (pintype "bidirectional"))
      (node (ref "U4") (pin "3") (pinfunction "VIN_3") (pintype "input"))
      (node (ref "U6") (pin "8") (pinfunction "VCC_8") (pintype "bidirectional"))
    )
    (net (code "53") (name "12V") (class "Default")
      (node (ref "C11") (pin "+") (pinfunction "+_+") (pintype "passive"))
      (node (ref "C12") (pin "1") (pinfunction "1_1") (pintype "passive"))
      (node (ref "D1") (pin "C") (pinfunction "C_C") (pintype "passive"))
      (node (ref "IC1") (pin "1") (pinfunction "IN_1") (pintype "input"))
      (node (ref "R20") (pin "2") (pinfunction "2_2") (pintype "passive"))
      (node (ref "R21") (pin "2") (pinfunction "2_2") (pintype "passive"))
    )
    (net (code "54") (name "AGND") (class "Default")
      (node (ref "C16") (pin "1") (pinfunction "1_1") (pintype "passive"))
      (node (ref "C3") (pin "1") (pinfunction "1_1") (pintype "passive"))
      (node (ref "C4") (pin "1") (pinfunction "1_1") (pintype "passive"))
      (node (ref "C5") (pin "1") (pinfunction "1_1") (pintype "passive"))
      (node (ref "C6") (pin "1") (pinfunction "1_1") (pintype "passive"))
      (node (ref "FB1") (pin "1") (pinfunction "1_1") (pintype "passive"))
      (node (ref "IC2") (pin "4") (pinfunction "P$V-_4") (pintype "bidirectional"))
      (node (ref "R24") (pin "2") (pinfunction "2_2") (pintype "passive"))
      (node (ref "R26") (pin "2") (pinfunction "2_2") (pintype "passive"))
      (node (ref "R29") (pin "1") (pinfunction "1_1") (pintype "passive"))
      (node (ref "U3") (pin "3") (pinfunction "GND_3") (pintype "passive"))
    )
    (net (code "55") (name "GND") (class "Default")
      (node (ref "BLE") (pin "13") (pinfunction "GND_13") (pintype "bidirectional"))
      (node (ref "BLE") (pin "14") (pinfunction "GND_14") (pintype "bidirectional"))
      (node (ref "BLE") (pin "21") (pinfunction "GND_21") (pintype "bidirectional"))
      (node (ref "BLE") (pin "22") (pinfunction "GND_22") (pintype "bidirectional"))
      (node (ref "BT1") (pin "2") (pinfunction "-_2") (pintype "power_in"))
      (node (ref "C1") (pin "1") (pinfunction "1_1") (pintype "passive"))
      (node (ref "C10") (pin "1") (pinfunction "1_1") (pintype "passive"))
      (node (ref "C11") (pin "-") (pinfunction "-_-") (pintype "passive"))
      (node (ref "C12") (pin "2") (pinfunction "2_2") (pintype "passive"))
      (node (ref "C13") (pin "-") (pinfunction "-_-") (pintype "passive"))
      (node (ref "C14") (pin "2") (pinfunction "2_2") (pintype "passive"))
      (node (ref "C15") (pin "2") (pinfunction "2_2") (pintype "passive"))
      (node (ref "C17") (pin "-") (pinfunction "-_-") (pintype "passive"))
      (node (ref "C18") (pin "2") (pinfunction "2_2") (pintype "passive"))
      (node (ref "C19") (pin "1") (pinfunction "1_1") (pintype "passive"))
      (node (ref "C2") (pin "1") (pinfunction "1_1") (pintype "passive"))
      (node (ref "C20") (pin "1") (pinfunction "1_1") (pintype "passive"))
      (node (ref "C21") (pin "1") (pinfunction "1_1") (pintype "passive"))
      (node (ref "C22") (pin "1") (pinfunction "1_1") (pintype "passive"))
      (node (ref "C23") (pin "1") (pinfunction "1_1") (pintype "passive"))
      (node (ref "C24") (pin "1") (pinfunction "1_1") (pintype "passive"))
      (node (ref "C25") (pin "1") (pinfunction "1_1") (pintype "passive"))
      (node (ref "C26") (pin "2") (pinfunction "2_2") (pintype "passive"))
      (node (ref "C27") (pin "2") (pinfunction "2_2") (pintype "passive"))
      (node (ref "C28") (pin "2") (pinfunction "2_2") (pintype "passive"))
      (node (ref "C29") (pin "1") (pinfunction "1_1") (pintype "passive"))
      (node (ref "C7") (pin "2") (pinfunction "2_2") (pintype "passive"))
      (node (ref "D109") (pin "A") (pinfunction "A_A") (pintype "passive"))
      (node (ref "D11") (pin "C") (pinfunction "C_C") (pintype "passive"))
      (node (ref "D2") (pin "3") (pinfunction "GND_3") (pintype "bidirectional"))
      (node (ref "D3") (pin "+") (pinfunction "+_+") (pintype "passive"))
      (node (ref "D4") (pin "+") (pinfunction "+_+") (pintype "passive"))
      (node (ref "D5") (pin "+") (pinfunction "+_+") (pintype "passive"))
      (node (ref "D6") (pin "+") (pinfunction "+_+") (pintype "passive"))
      (node (ref "D7") (pin "A") (pinfunction "A_A") (pintype "passive"))
      (node (ref "FB1") (pin "2") (pinfunction "2_2") (pintype "passive"))
      (node (ref "IC1") (pin "3") (pinfunction "GND_3") (pintype "power_in"))
      (node (ref "IC1") (pin "6") (pinfunction "GND_6") (pintype "power_in"))
      (node (ref "IC3") (pin "11") (pinfunction "GND_11") (pintype "power_in"))
      (node (ref "IC3") (pin "32") (pinfunction "GND1_32") (pintype "power_in"))
      (node (ref "IC3") (pin "62") (pinfunction "GND2_62") (pintype "power_in"))
      (node (ref "IC3") (pin "81") (pinfunction "GND3_81") (pintype "power_in"))
      (node (ref "IC3") (pin "99") (pinfunction "AGND_99") (pintype "power_in"))
      (node (ref "IC4") (pin "2") (pinfunction "ANODE,CATHODE_1_2") (pintype "bidirectional"))
      (node (ref "IC4") (pin "4") (pinfunction "ANODE,CATHODE_2_4") (pintype "bidirectional"))
      (node (ref "IC4") (pin "6") (pinfunction "ANODE,CATHODE_3_6") (pintype "bidirectional"))
      (node (ref "IC4") (pin "8") (pinfunction "ANODE,CATHODE_4_8") (pintype "bidirectional"))
      (node (ref "J1") (pin "5") (pinfunction "5_5") (pintype "passive"))
      (node (ref "J2") (pin "6") (pinfunction "6_6") (pintype "passive"))
      (node (ref "PROG") (pin "4") (pinfunction "GND_4") (pintype "passive"))
      (node (ref "Q1") (pin "2") (pinfunction "E_2") (pintype "passive"))
      (node (ref "R11") (pin "1") (pinfunction "1_1") (pintype "passive"))
      (node (ref "R13") (pin "2") (pinfunction "2_2") (pintype "passive"))
      (node (ref "R14") (pin "2") (pinfunction "2_2") (pintype "passive"))
      (node (ref "R15") (pin "2") (pinfunction "2_2") (pintype "passive"))
      (node (ref "R16") (pin "2") (pinfunction "2_2") (pintype "passive"))
      (node (ref "R17") (pin "1") (pinfunction "1_1") (pintype "passive"))
      (node (ref "R22") (pin "1") (pinfunction "1_1") (pintype "passive"))
      (node (ref "R28") (pin "2") (pinfunction "2_2") (pintype "passive"))
      (node (ref "R31") (pin "1") (pinfunction "1_1") (pintype "passive"))
      (node (ref "R35") (pin "1") (pinfunction "1_1") (pintype "passive"))
      (node (ref "R48") (pin "2") (pinfunction "2_2") (pintype "passive"))
      (node (ref "R49") (pin "2") (pinfunction "2_2") (pintype "passive"))
      (node (ref "R50") (pin "2") (pinfunction "2_2") (pintype "passive"))
      (node (ref "R51") (pin "2") (pinfunction "2_2") (pintype "passive"))
      (node (ref "R62") (pin "1") (pinfunction "1_1") (pintype "passive"))
      (node (ref "S1") (pin "1") (pinfunction "1_1") (pintype "passive"))
      (node (ref "S2") (pin "2") (pinfunction "2_2") (pintype "passive"))
      (node (ref "SD1") (pin "6") (pinfunction "VSS_6") (pintype "power_in"))
      (node (ref "SD1") (pin "S1") (pinfunction "S1_S1") (pintype "passive"))
      (node (ref "SD1") (pin "S2") (pinfunction "S2_S2") (pintype "passive"))
      (node (ref "SD1") (pin "S3") (pinfunction "S3_S3") (pintype "passive"))
      (node (ref "SD1") (pin "S4") (pinfunction "S4_S4") (pintype "passive"))
      (node (ref "U1") (pin "15") (pinfunction "GND_15") (pintype "bidirectional"))
      (node (ref "U10") (pin "1") (pinfunction "~{OE}_1") (pintype "input"))
      (node (ref "U10") (pin "3") (pinfunction "GND_3") (pintype "passive"))
      (node (ref "U2") (pin "5") (pinfunction "GND_5") (pintype "bidirectional"))
      (node (ref "U4") (pin "1") (pinfunction "ADJ/GND_1") (pintype "power_in"))
      (node (ref "U5") (pin "10") (pinfunction "GND_10") (pintype "bidirectional"))
      (node (ref "U5") (pin "19") (pinfunction "/OE_19") (pintype "bidirectional"))
      (node (ref "U6") (pin "4") (pinfunction "GND_4") (pintype "bidirectional"))
      (node (ref "U7") (pin "2") (pinfunction "K_2") (pintype "passive"))
      (node (ref "U8") (pin "2") (pinfunction "K_2") (pintype "passive"))
      (node (ref "U9") (pin "2") (pinfunction "K_2") (pintype "passive"))
      (node (ref "WIFI") (pin "J12") (pinfunction "GND_J12") (pintype "power_in"))
      (node (ref "WIFI") (pin "J28") (pinfunction "GND_J28") (pintype "power_in"))
      (node (ref "WIFI") (pin "J9") (pinfunction "GND_J9") (pintype "bidirectional"))
      (node (ref "WIFI") (pin "MTGND") (pinfunction "GND_MTGND") (pintype "power_in"))
      (node (ref "X1") (pin "3") (pinfunction "1_3") (pintype "passive"))
      (node (ref "X1") (pin "4") (pinfunction "1_4") (pintype "passive"))
    )
    (net (code "56") (name "GND-ISO") (class "Default")
      (node (ref "Q5") (pin "3") (pinfunction "E_3") (pintype "bidirectional"))
      (node (ref "Q6") (pin "2") (pinfunction "E_2") (pintype "passive"))
      (node (ref "Q7") (pin "2") (pinfunction "E_2") (pintype "passive"))
      (node (ref "X6") (pin "1") (pinfunction "1_1") (pintype "passive"))
    )
    (net (code "57") (name "Net-(BLE-KEY)") (class "Default")
      (node (ref "BLE") (pin "23") (pinfunction "KEY_23") (pintype "bidirectional"))
      (node (ref "R52") (pin "1") (pinfunction "1_1") (pintype "passive"))
      (node (ref "R56") (pin "1") (pinfunction "1_1") (pintype "passive"))
      (node (ref "S2") (pin "1") (pinfunction "1_1") (pintype "passive"))
    )
    (net (code "58") (name "Net-(BLE-PIO5)") (class "Default")
      (node (ref "BLE") (pin "28") (pinfunction "PIO5_28") (pintype "bidirectional"))
      (node (ref "R62") (pin "2") (pinfunction "2_2") (pintype "passive"))
    )
    (net (code "59") (name "Net-(BT1-+)") (class "Default")
      (node (ref "BT1") (pin "1") (pinfunction "+_1") (pintype "power_in"))
      (node (ref "U6") (pin "3") (pinfunction "VBATT_3") (pintype "bidirectional"))
    )
    (net (code "60") (name "Net-(C13-Pad+)") (class "Default")
      (node (ref "C13") (pin "+") (pinfunction "+_+") (pintype "passive"))
      (node (ref "C14") (pin "1") (pinfunction "1_1") (pintype "passive"))
      (node (ref "F3") (pin "1") (pinfunction "1_1") (pintype "bidirectional"))
      (node (ref "L1") (pin "1") (pinfunction "1_1") (pintype "passive"))
      (node (ref "R19") (pin "2") (pinfunction "2_2") (pintype "passive"))
    )
    (net (code "61") (name "Net-(D2-IO1)") (class "Default")
      (node (ref "D2") (pin "1") (pinfunction "IO1_1") (pintype "bidirectional"))
      (node (ref "F2") (pin "1") (pinfunction "1_1") (pintype "bidirectional"))
      (node (ref "R12") (pin "1") (pinfunction "1_1") (pintype "passive"))
      (node (ref "R23") (pin "2") (pinfunction "2_2") (pintype "passive"))
      (node (ref "U2") (pin "6") (pinfunction "A_6") (pintype "bidirectional"))
    )
    (net (code "62") (name "Net-(D2-IO2)") (class "Default")
      (node (ref "D2") (pin "2") (pinfunction "IO2_2") (pintype "bidirectional"))
      (node (ref "F1") (pin "1") (pinfunction "1_1") (pintype "bidirectional"))
      (node (ref "R11") (pin "2") (pinfunction "2_2") (pintype "passive"))
      (node (ref "R23") (pin "1") (pinfunction "1_1") (pintype "passive"))
      (node (ref "U2") (pin "7") (pinfunction "B_7") (pintype "bidirectional"))
    )
    (net (code "63") (name "Net-(D8-PadA)") (class "Default")
      (node (ref "D8") (pin "A") (pinfunction "A_A") (pintype "passive"))
      (node (ref "R38") (pin "2") (pinfunction "2_2") (pintype "passive"))
    )
    (net (code "64") (name "Net-(D9-PadA)") (class "Default")
      (node (ref "D9") (pin "A") (pinfunction "A_A") (pintype "passive"))
      (node (ref "R40") (pin "2") (pinfunction "2_2") (pintype "passive"))
    )
    (net (code "65") (name "Net-(D10-PadA)") (class "Default")
      (node (ref "D10") (pin "A") (pinfunction "A_A") (pintype "passive"))
      (node (ref "R42") (pin "2") (pinfunction "2_2") (pintype "passive"))
    )
    (net (code "66") (name "Net-(D11-PadA)") (class "Default")
      (node (ref "D11") (pin "A") (pinfunction "A_A") (pintype "passive"))
      (node (ref "R60") (pin "2") (pinfunction "2_2") (pintype "passive"))
    )
    (net (code "67") (name "Net-(D106-PadA)") (class "Default")
      (node (ref "D106") (pin "A") (pinfunction "A_A") (pintype "passive"))
      (node (ref "X5") (pin "1") (pinfunction "1_1") (pintype "passive"))
    )
    (net (code "68") (name "Net-(D107-PadC)") (class "Default")
      (node (ref "D107") (pin "C") (pinfunction "C_C") (pintype "passive"))
      (node (ref "R6") (pin "2") (pinfunction "2_2") (pintype "passive"))
      (node (ref "R9") (pin "2") (pinfunction "2_2") (pintype "passive"))
    )
    (net (code "69") (name "Net-(D108-PadC)") (class "Default")
      (node (ref "D108") (pin "C") (pinfunction "C_C") (pintype "passive"))
      (node (ref "R5") (pin "2") (pinfunction "2_2") (pintype "passive"))
      (node (ref "R7") (pin "2") (pinfunction "2_2") (pintype "passive"))
    )
    (net (code "70") (name "Net-(F2-Pad2)") (class "Default")
      (node (ref "F2") (pin "2") (pinfunction "2_2") (pintype "bidirectional"))
      (node (ref "X2") (pin "1") (pinfunction "1_1") (pintype "passive"))
    )
    (net (code "71") (name "Net-(IC1-FB)") (class "Default")
      (node (ref "IC1") (pin "4") (pinfunction "FB_4") (pintype "input"))
      (node (ref "R17") (pin "2") (pinfunction "2_2") (pintype "passive"))
      (node (ref "R18") (pin "1") (pinfunction "1_1") (pintype "passive"))
    )
    (net (code "72") (name "Net-(IC1-OUT)") (class "Default")
      (node (ref "D7") (pin "C") (pinfunction "C_C") (pintype "passive"))
      (node (ref "IC1") (pin "2") (pinfunction "OUT_2") (pintype "output"))
      (node (ref "L1") (pin "2") (pinfunction "2_2") (pintype "passive"))
    )
    (net (code "73") (name "Net-(IC2A-+IN)") (class "Default")
      (node (ref "C5") (pin "2") (pinfunction "2_2") (pintype "passive"))
      (node (ref "DOV101") (pin "A") (pinfunction "A_A") (pintype "passive"))
      (node (ref "IC2") (pin "3") (pinfunction "+IN_3") (pintype "input"))
      (node (ref "R26") (pin "1") (pinfunction "1_1") (pintype "passive"))
      (node (ref "R9") (pin "1") (pinfunction "1_1") (pintype "passive"))
    )
    (net (code "74") (name "Net-(IC2A--IN)") (class "Default")
      (node (ref "DOV100") (pin "A") (pinfunction "A_A") (pintype "passive"))
      (node (ref "IC2") (pin "2") (pinfunction "-IN_2") (pintype "input"))
      (node (ref "R10") (pin "1") (pinfunction "1_1") (pintype "passive"))
      (node (ref "R27") (pin "2") (pinfunction "2_2") (pintype "passive"))
    )
    (net (code "75") (name "Net-(IC2B-+IN)") (class "Default")
      (node (ref "C3") (pin "2") (pinfunction "2_2") (pintype "passive"))
      (node (ref "DOV103") (pin "A") (pinfunction "A_A") (pintype "passive"))
      (node (ref "IC2") (pin "5") (pinfunction "+IN_5") (pintype "input"))
      (node (ref "R24") (pin "1") (pinfunction "1_1") (pintype "passive"))
      (node (ref "R7") (pin "1") (pinfunction "1_1") (pintype "passive"))
    )
    (net (code "76") (name "Net-(IC2B--IN)") (class "Default")
      (node (ref "DOV102") (pin "A") (pinfunction "A_A") (pintype "passive"))
      (node (ref "IC2") (pin "6") (pinfunction "-IN_6") (pintype "input"))
      (node (ref "R25") (pin "2") (pinfunction "2_2") (pintype "passive"))
      (node (ref "R8") (pin "1") (pinfunction "1_1") (pintype "passive"))
    )
    (net (code "77") (name "Net-(IC3-AREF)") (class "Default")
      (node (ref "C15") (pin "1") (pinfunction "1_1") (pintype "passive"))
      (node (ref "IC3") (pin "98") (pinfunction "AREF_98") (pintype "bidirectional"))
    )
    (net (code "78") (name "Net-(IC3-XTAL1)") (class "Default")
      (node (ref "C25") (pin "2") (pinfunction "2_2") (pintype "passive"))
      (node (ref "IC3") (pin "34") (pinfunction "XTAL1_34") (pintype "input"))
      (node (ref "Q2") (pin "1") (pinfunction "1_1") (pintype "passive"))
      (node (ref "R43") (pin "1") (pinfunction "1_1") (pintype "passive"))
    )
    (net (code "79") (name "Net-(IC3-XTAL2)") (class "Default")
      (node (ref "C24") (pin "2") (pinfunction "2_2") (pintype "passive"))
      (node (ref "IC3") (pin "33") (pinfunction "XTAL2_33") (pintype "output"))
      (node (ref "Q2") (pin "2") (pinfunction "2_2") (pintype "passive"))
      (node (ref "R43") (pin "2") (pinfunction "2_2") (pintype "passive"))
    )
    (net (code "80") (name "Net-(IC4-CATHODE,ANODE_1)") (class "Default")
      (node (ref "IC4") (pin "1") (pinfunction "CATHODE,ANODE_1_1") (pintype "bidirectional"))
      (node (ref "RN1") (pin "4") (pinfunction "1_4") (pintype "passive"))
    )
    (net (code "81") (name "Net-(IC4-CATHODE,ANODE_2)") (class "Default")
      (node (ref "IC4") (pin "3") (pinfunction "CATHODE,ANODE_2_3") (pintype "bidirectional"))
      (node (ref "RN1") (pin "3") (pinfunction "1_3") (pintype "passive"))
    )
    (net (code "82") (name "Net-(IC4-CATHODE,ANODE_3)") (class "Default")
      (node (ref "IC4") (pin "5") (pinfunction "CATHODE,ANODE_3_5") (pintype "bidirectional"))
      (node (ref "RN1") (pin "2") (pinfunction "1_2") (pintype "passive"))
    )
    (net (code "83") (name "Net-(IC4-CATHODE,ANODE_4)") (class "Default")
      (node (ref "IC4") (pin "7") (pinfunction "CATHODE,ANODE_4_7") (pintype "bidirectional"))
      (node (ref "RN1") (pin "1") (pinfunction "1_1") (pintype "passive"))
    )
    (net (code "84") (name "Net-(LED1-PadC)") (class "Default")
      (node (ref "LED1") (pin "C") (pinfunction "C_C") (pintype "passive"))
      (node (ref "R31") (pin "2") (pinfunction "2_2") (pintype "passive"))
    )
    (net (code "85") (name "Net-(Q1-B)") (class "Default")
      (node (ref "Q1") (pin "1") (pinfunction "B_1") (pintype "passive"))
      (node (ref "R22") (pin "2") (pinfunction "2_2") (pintype "passive"))
      (node (ref "ZENER") (pin "1") (pinfunction "1_1") (pintype "passive"))
    )
    (net (code "86") (name "Net-(Q3-2)") (class "Default")
      (node (ref "Q3") (pin "4") (pinfunction "2_4") (pintype "passive"))
      (node (ref "U6") (pin "2") (pinfunction "X2_2") (pintype "bidirectional"))
    )
    (net (code "87") (name "Net-(Q5-B)") (class "Default")
      (node (ref "Q5") (pin "1") (pinfunction "B_1") (pintype "bidirectional"))
      (node (ref "R63") (pin "1") (pinfunction "1_1") (pintype "passive"))
    )
    (net (code "88") (name "Net-(Q5-C)") (class "Default")
      (node (ref "D102") (pin "A") (pinfunction "A_A") (pintype "passive"))
      (node (ref "Q5") (pin "2") (pinfunction "C_2") (pintype "bidirectional"))
      (node (ref "X6") (pin "4") (pinfunction "1_4") (pintype "passive"))
    )
    (net (code "89") (name "Net-(Q6-B)") (class "Default")
      (node (ref "Q6") (pin "1") (pinfunction "B_1") (pintype "passive"))
      (node (ref "R64") (pin "1") (pinfunction "1_1") (pintype "passive"))
    )
    (net (code "90") (name "Net-(Q6-C)") (class "Default")
      (node (ref "D101") (pin "A") (pinfunction "A_A") (pintype "passive"))
      (node (ref "Q6") (pin "3") (pinfunction "C_3") (pintype "passive"))
      (node (ref "X7") (pin "1") (pinfunction "1_1") (pintype "passive"))
    )
    (net (code "91") (name "Net-(Q7-B)") (class "Default")
      (node (ref "Q7") (pin "1") (pinfunction "B_1") (pintype "passive"))
      (node (ref "R65") (pin "1") (pinfunction "1_1") (pintype "passive"))
    )
    (net (code "92") (name "Net-(Q7-C)") (class "Default")
      (node (ref "D100") (pin "A") (pinfunction "A_A") (pintype "passive"))
      (node (ref "Q7") (pin "3") (pinfunction "C_3") (pintype "passive"))
      (node (ref "X7") (pin "3") (pinfunction "1_3") (pintype "passive"))
    )
    (net (code "93") (name "Net-(R4-Pad2)") (class "Default")
      (node (ref "R4") (pin "2") (pinfunction "2_2") (pintype "passive"))
      (node (ref "X3") (pin "1") (pinfunction "1_1") (pintype "passive"))
    )
    (net (code "94") (name "Net-(R10-Pad2)") (class "Default")
      (node (ref "R10") (pin "2") (pinfunction "2_2") (pintype "passive"))
      (node (ref "R6") (pin "1") (pinfunction "1_1") (pintype "passive"))
      (node (ref "X4") (pin "1") (pinfunction "1_1") (pintype "passive"))
    )
    (net (code "95") (name "Net-(R18-Pad2)") (class "Default")
      (node (ref "R18") (pin "2") (pinfunction "2_2") (pintype "passive"))
      (node (ref "R19") (pin "1") (pinfunction "1_1") (pintype "passive"))
    )
    (net (code "96") (name "Net-(R20-Pad1)") (class "Default")
      (node (ref "R20") (pin "1") (pinfunction "1_1") (pintype "passive"))
      (node (ref "ZENER") (pin "2") (pinfunction "2_2") (pintype "passive"))
    )
    (net (code "97") (name "Net-(RN1A-2)") (class "Default")
      (node (ref "D103") (pin "C") (pinfunction "C_C") (pintype "passive"))
      (node (ref "RN1") (pin "8") (pinfunction "2_8") (pintype "passive"))
    )
    (net (code "98") (name "Net-(RN1B-2)") (class "Default")
      (node (ref "D104") (pin "C") (pinfunction "C_C") (pintype "passive"))
      (node (ref "RN1") (pin "7") (pinfunction "2_7") (pintype "passive"))
    )
    (net (code "99") (name "Net-(RN1C-2)") (class "Default")
      (node (ref "D105") (pin "C") (pinfunction "C_C") (pintype "passive"))
      (node (ref "RN1") (pin "6") (pinfunction "2_6") (pintype "passive"))
    )
    (net (code "100") (name "Net-(RN1D-2)") (class "Default")
      (node (ref "D106") (pin "C") (pinfunction "C_C") (pintype "passive"))
      (node (ref "RN1") (pin "5") (pinfunction "2_5") (pintype "passive"))
    )
    (net (code "101") (name "Net-(U1-C1+)") (class "Default")
      (node (ref "C8") (pin "2") (pinfunction "2_2") (pintype "passive"))
      (node (ref "U1") (pin "1") (pinfunction "C1+_1") (pintype "bidirectional"))
    )
    (net (code "102") (name "Net-(U1-C1-)") (class "Default")
      (node (ref "C8") (pin "1") (pinfunction "1_1") (pintype "passive"))
      (node (ref "U1") (pin "3") (pinfunction "C1-_3") (pintype "bidirectional"))
    )
    (net (code "103") (name "Net-(U1-C2+)") (class "Default")
      (node (ref "C9") (pin "1") (pinfunction "1_1") (pintype "passive"))
      (node (ref "U1") (pin "4") (pinfunction "C2+_4") (pintype "bidirectional"))
    )
    (net (code "104") (name "Net-(U1-C2-)") (class "Default")
      (node (ref "C9") (pin "2") (pinfunction "2_2") (pintype "passive"))
      (node (ref "U1") (pin "5") (pinfunction "C2-_5") (pintype "bidirectional"))
    )
    (net (code "105") (name "Net-(U1-V+)") (class "Default")
      (node (ref "C2") (pin "2") (pinfunction "2_2") (pintype "passive"))
      (node (ref "U1") (pin "2") (pinfunction "V+_2") (pintype "bidirectional"))
    )
    (net (code "106") (name "Net-(U1-V-)") (class "Default")
      (node (ref "C10") (pin "2") (pinfunction "2_2") (pintype "passive"))
      (node (ref "U1") (pin "6") (pinfunction "V-_6") (pintype "bidirectional"))
    )
    (net (code "107") (name "Net-(U3-ADDR)") (class "Default")
      (node (ref "R29") (pin "2") (pinfunction "2_2") (pintype "passive"))
      (node (ref "U3") (pin "1") (pinfunction "ADDR_1") (pintype "input"))
    )
    (net (code "108") (name "Net-(U3-ALERT{slash}RDY)") (class "Default")
      (node (ref "R30") (pin "1") (pinfunction "1_1") (pintype "passive"))
      (node (ref "U3") (pin "2") (pinfunction "ALERT/RDY_2") (pintype "input"))
    )
    (net (code "109") (name "Net-(U6-X1)") (class "Default")
      (node (ref "Q3") (pin "1") (pinfunction "1_1") (pintype "passive"))
      (node (ref "U6") (pin "1") (pinfunction "X1_1") (pintype "bidirectional"))
    )
    (net (code "110") (name "Net-(U7-A)") (class "Default")
      (node (ref "R57") (pin "1") (pinfunction "1_1") (pintype "passive"))
      (node (ref "U7") (pin "1") (pinfunction "A_1") (pintype "passive"))
    )
    (net (code "111") (name "Net-(U7-E)") (class "Default")
      (node (ref "R63") (pin "2") (pinfunction "2_2") (pintype "passive"))
      (node (ref "U7") (pin "3") (pinfunction "E_3") (pintype "passive"))
    )
    (net (code "112") (name "Net-(U8-A)") (class "Default")
      (node (ref "R58") (pin "1") (pinfunction "1_1") (pintype "passive"))
      (node (ref "U8") (pin "1") (pinfunction "A_1") (pintype "passive"))
    )
    (net (code "113") (name "Net-(U8-E)") (class "Default")
      (node (ref "R64") (pin "2") (pinfunction "2_2") (pintype "passive"))
      (node (ref "U8") (pin "3") (pinfunction "E_3") (pintype "passive"))
    )
    (net (code "114") (name "Net-(U9-A)") (class "Default")
      (node (ref "R59") (pin "1") (pinfunction "1_1") (pintype "passive"))
      (node (ref "U9") (pin "1") (pinfunction "A_1") (pintype "passive"))
    )
    (net (code "115") (name "Net-(U9-E)") (class "Default")
      (node (ref "R65") (pin "2") (pinfunction "2_2") (pintype "passive"))
      (node (ref "U9") (pin "3") (pinfunction "E_3") (pintype "passive"))
    )
    (net (code "116") (name "Net-(WIFI-CHIP_EN)") (class "Default")
      (node (ref "R44") (pin "2") (pinfunction "2_2") (pintype "passive"))
      (node (ref "R45") (pin "1") (pinfunction "1_1") (pintype "passive"))
      (node (ref "WIFI") (pin "J22") (pinfunction "CHIP_EN_J22") (pintype "input"))
    )
    (net (code "117") (name "Net-(WIFI-GPIO15)") (class "Default")
      (node (ref "D10") (pin "C") (pinfunction "C_C") (pintype "passive"))
      (node (ref "WIFI") (pin "J26") (pinfunction "GPIO15_J26") (pintype "bidirectional"))
    )
    (net (code "118") (name "Net-(WIFI-GPIO16)") (class "Default")
      (node (ref "D9") (pin "C") (pinfunction "C_C") (pintype "passive"))
      (node (ref "WIFI") (pin "J27") (pinfunction "GPIO16_J27") (pintype "bidirectional"))
    )
    (net (code "119") (name "Net-(WIFI-GPIO18)") (class "Default")
      (node (ref "D8") (pin "C") (pinfunction "C_C") (pintype "passive"))
      (node (ref "WIFI") (pin "J1") (pinfunction "GPIO18_J1") (pintype "bidirectional"))
    )
    (net (code "120") (name "Net-(WIFI-SPI_CFG)") (class "Default")
      (node (ref "R53") (pin "1") (pinfunction "1_1") (pintype "passive"))
      (node (ref "WIFI") (pin "J10") (pinfunction "SPI_CFG_J10") (pintype "input"))
    )
    (net (code "121") (name "Net-(WIFI-WAKE)") (class "Default")
      (node (ref "R54") (pin "1") (pinfunction "1_1") (pintype "passive"))
      (node (ref "WIFI") (pin "J11") (pinfunction "WAKE_J11") (pintype "input"))
    )
    (net (code "122") (name "Net-(X1B-1)") (class "Default")
      (node (ref "D1") (pin "A") (pinfunction "A_A") (pintype "passive"))
      (node (ref "D109") (pin "C") (pinfunction "C_C") (pintype "passive"))
      (node (ref "X1") (pin "1") (pinfunction "1_1") (pintype "passive"))
      (node (ref "X1") (pin "2") (pinfunction "1_2") (pintype "passive"))
    )
    (net (code "123") (name "Net-(X2B-1)") (class "Default")
      (node (ref "F1") (pin "2") (pinfunction "2_2") (pintype "bidirectional"))
      (node (ref "X2") (pin "2") (pinfunction "1_2") (pintype "passive"))
    )
    (net (code "124") (name "Net-(X3B-1)") (class "Default")
      (node (ref "R3") (pin "2") (pinfunction "2_2") (pintype "passive"))
      (node (ref "X3") (pin "2") (pinfunction "1_2") (pintype "passive"))
    )
    (net (code "125") (name "Net-(X3C-1)") (class "Default")
      (node (ref "R2") (pin "2") (pinfunction "2_2") (pintype "passive"))
      (node (ref "X3") (pin "3") (pinfunction "1_3") (pintype "passive"))
    )
    (net (code "126") (name "Net-(X3D-1)") (class "Default")
      (node (ref "R1") (pin "2") (pinfunction "2_2") (pintype "passive"))
      (node (ref "X3") (pin "4") (pinfunction "1_4") (pintype "passive"))
    )
    (net (code "127") (name "Net-(X4B-1)") (class "Default")
      (node (ref "D107") (pin "A") (pinfunction "A_A") (pintype "passive"))
      (node (ref "X4") (pin "2") (pinfunction "1_2") (pintype "passive"))
    )
    (net (code "128") (name "Net-(X4C-1)") (class "Default")
      (node (ref "R5") (pin "1") (pinfunction "1_1") (pintype "passive"))
      (node (ref "R8") (pin "2") (pinfunction "2_2") (pintype "passive"))
      (node (ref "X4") (pin "3") (pinfunction "1_3") (pintype "passive"))
    )
    (net (code "129") (name "Net-(X4D-1)") (class "Default")
      (node (ref "D108") (pin "A") (pinfunction "A_A") (pintype "passive"))
      (node (ref "X4") (pin "4") (pinfunction "1_4") (pintype "passive"))
    )
    (net (code "130") (name "Net-(X5B-1)") (class "Default")
      (node (ref "D105") (pin "A") (pinfunction "A_A") (pintype "passive"))
      (node (ref "X5") (pin "2") (pinfunction "1_2") (pintype "passive"))
    )
    (net (code "131") (name "Net-(X5C-1)") (class "Default")
      (node (ref "D104") (pin "A") (pinfunction "A_A") (pintype "passive"))
      (node (ref "X5") (pin "3") (pinfunction "1_3") (pintype "passive"))
    )
    (net (code "132") (name "Net-(X5D-1)") (class "Default")
      (node (ref "D103") (pin "A") (pinfunction "A_A") (pintype "passive"))
      (node (ref "X5") (pin "4") (pinfunction "1_4") (pintype "passive"))
    )
    (net (code "133") (name "VCCA") (class "Default")
      (node (ref "C16") (pin "2") (pinfunction "2_2") (pintype "passive"))
      (node (ref "DOV100") (pin "C") (pinfunction "C_C") (pintype "passive"))
      (node (ref "DOV101") (pin "C") (pinfunction "C_C") (pintype "passive"))
      (node (ref "DOV102") (pin "C") (pinfunction "C_C") (pintype "passive"))
      (node (ref "DOV103") (pin "C") (pinfunction "C_C") (pintype "passive"))
      (node (ref "FB2") (pin "1") (pinfunction "1_1") (pintype "passive"))
      (node (ref "IC2") (pin "8") (pinfunction "P$V+_8") (pintype "bidirectional"))
      (node (ref "R30") (pin "2") (pinfunction "2_2") (pintype "passive"))
      (node (ref "U3") (pin "8") (pinfunction "VDD_8") (pintype "power_in"))
    )
    (net (code "134") (name "unconnected-(BLE-NC5-Pad5)") (class "Default")
      (node (ref "BLE") (pin "5") (pinfunction "NC5_5") (pintype "bidirectional"))
    )
    (net (code "135") (name "unconnected-(BLE-NC6-Pad6)") (class "Default")
      (node (ref "BLE") (pin "6") (pinfunction "NC6_6") (pintype "bidirectional"))
    )
    (net (code "136") (name "unconnected-(BLE-NC7-Pad$7)") (class "Default")
      (node (ref "BLE") (pin "$7") (pinfunction "NC7_$7") (pintype "bidirectional"))
    )
    (net (code "137") (name "unconnected-(BLE-NC8-Pad8)") (class "Default")
      (node (ref "BLE") (pin "8") (pinfunction "NC8_8") (pintype "bidirectional"))
    )
    (net (code "138") (name "unconnected-(BLE-NC9-Pad9)") (class "Default")
      (node (ref "BLE") (pin "9") (pinfunction "NC9_9") (pintype "bidirectional"))
    )
    (net (code "139") (name "unconnected-(BLE-NC10-Pad10)") (class "Default")
      (node (ref "BLE") (pin "10") (pinfunction "NC10_10") (pintype "bidirectional"))
    )
    (net (code "140") (name "unconnected-(BLE-NC16-Pad16)") (class "Default")
      (node (ref "BLE") (pin "16") (pinfunction "NC16_16") (pintype "bidirectional"))
    )
    (net (code "141") (name "unconnected-(BLE-NC17-Pad17)") (class "Default")
      (node (ref "BLE") (pin "17") (pinfunction "NC17_17") (pintype "bidirectional"))
    )
    (net (code "142") (name "unconnected-(BLE-NC18-Pad18)") (class "Default")
      (node (ref "BLE") (pin "18") (pinfunction "NC18_18") (pintype "bidirectional"))
    )
    (net (code "143") (name "unconnected-(BLE-NC19-Pad19)") (class "Default")
      (node (ref "BLE") (pin "19") (pinfunction "NC19_19") (pintype "bidirectional"))
    )
    (net (code "144") (name "unconnected-(BLE-PIO2-Pad25)") (class "Default")
      (node (ref "BLE") (pin "25") (pinfunction "PIO2_25") (pintype "bidirectional"))
    )
    (net (code "145") (name "unconnected-(BLE-PIO3-Pad26)") (class "Default")
      (node (ref "BLE") (pin "26") (pinfunction "PIO3_26") (pintype "bidirectional"))
    )
    (net (code "146") (name "unconnected-(BLE-PIO4-Pad27)") (class "Default")
      (node (ref "BLE") (pin "27") (pinfunction "PIO4_27") (pintype "bidirectional"))
    )
    (net (code "147") (name "unconnected-(BLE-PIO6-Pad29)") (class "Default")
      (node (ref "BLE") (pin "29") (pinfunction "PIO6_29") (pintype "bidirectional"))
    )
    (net (code "148") (name "unconnected-(BLE-PIO7-Pad30)") (class "Default")
      (node (ref "BLE") (pin "30") (pinfunction "PIO7_30") (pintype "bidirectional"))
    )
    (net (code "149") (name "unconnected-(BLE-PIO8-Pad31)") (class "Default")
      (node (ref "BLE") (pin "31") (pinfunction "PIO8_31") (pintype "bidirectional"))
    )
    (net (code "150") (name "unconnected-(BLE-PIO9-Pad32)") (class "Default")
      (node (ref "BLE") (pin "32") (pinfunction "PIO9_32") (pintype "bidirectional"))
    )
    (net (code "151") (name "unconnected-(BLE-PIO10-Pad33)") (class "Default")
      (node (ref "BLE") (pin "33") (pinfunction "PIO10_33") (pintype "bidirectional"))
    )
    (net (code "152") (name "unconnected-(BLE-PIO11-Pad34)") (class "Default")
      (node (ref "BLE") (pin "34") (pinfunction "PIO11_34") (pintype "bidirectional"))
    )
    (net (code "153") (name "unconnected-(BLE-RESET-Pad11)") (class "Default")
      (node (ref "BLE") (pin "11") (pinfunction "RESET_11") (pintype "bidirectional"))
    )
    (net (code "154") (name "unconnected-(BLE-UART_CTS-Pad3)") (class "Default")
      (node (ref "BLE") (pin "3") (pinfunction "UART_CTS_3") (pintype "bidirectional"))
    )
    (net (code "155") (name "unconnected-(BLE-UART_RTS-Pad4)") (class "Default")
      (node (ref "BLE") (pin "4") (pinfunction "UART_RTS_4") (pintype "bidirectional"))
    )
    (net (code "156") (name "unconnected-(BLE-USB_D+-Pad20)") (class "Default")
      (node (ref "BLE") (pin "20") (pinfunction "USB_D+_20") (pintype "bidirectional"))
    )
    (net (code "157") (name "unconnected-(BLE-USB_D--Pad15)") (class "Default")
      (node (ref "BLE") (pin "15") (pinfunction "USB_D-_15") (pintype "bidirectional"))
    )
    (net (code "158") (name "unconnected-(IC3-(A11)PC3-Pad56)") (class "Default")
      (node (ref "IC3") (pin "56") (pinfunction "(A11)PC3_56") (pintype "bidirectional"))
    )
    (net (code "159") (name "unconnected-(IC3-(A12)PC4-Pad57)") (class "Default")
      (node (ref "IC3") (pin "57") (pinfunction "(A12)PC4_57") (pintype "bidirectional"))
    )
    (net (code "160") (name "unconnected-(IC3-(A13)PC5-Pad58)") (class "Default")
      (node (ref "IC3") (pin "58") (pinfunction "(A13)PC5_58") (pintype "bidirectional"))
    )
    (net (code "161") (name "unconnected-(IC3-(A14)PC6-Pad59)") (class "Default")
      (node (ref "IC3") (pin "59") (pinfunction "(A14)PC6_59") (pintype "bidirectional"))
    )
    (net (code "162") (name "unconnected-(IC3-(A15)PC7-Pad60)") (class "Default")
      (node (ref "IC3") (pin "60") (pinfunction "(A15)PC7_60") (pintype "bidirectional"))
    )
    (net (code "163") (name "unconnected-(IC3-(AD0)PA0-Pad78)") (class "Default")
      (node (ref "IC3") (pin "78") (pinfunction "(AD0)PA0_78") (pintype "bidirectional"))
    )
    (net (code "164") (name "unconnected-(IC3-(AD1)PA1-Pad77)") (class "Default")
      (node (ref "IC3") (pin "77") (pinfunction "(AD1)PA1_77") (pintype "bidirectional"))
    )
    (net (code "165") (name "unconnected-(IC3-(AD3)PA3-Pad75)") (class "Default")
      (node (ref "IC3") (pin "75") (pinfunction "(AD3)PA3_75") (pintype "bidirectional"))
    )
    (net (code "166") (name "unconnected-(IC3-(AD4)PA4-Pad74)") (class "Default")
      (node (ref "IC3") (pin "74") (pinfunction "(AD4)PA4_74") (pintype "bidirectional"))
    )
    (net (code "167") (name "unconnected-(IC3-(AD5)PA5-Pad73)") (class "Default")
      (node (ref "IC3") (pin "73") (pinfunction "(AD5)PA5_73") (pintype "bidirectional"))
    )
    (net (code "168") (name "unconnected-(IC3-(AD6)PA6-Pad72)") (class "Default")
      (node (ref "IC3") (pin "72") (pinfunction "(AD6)PA6_72") (pintype "bidirectional"))
    )
    (net (code "169") (name "unconnected-(IC3-(AD7)PA7-Pad71)") (class "Default")
      (node (ref "IC3") (pin "71") (pinfunction "(AD7)PA7_71") (pintype "bidirectional"))
    )
    (net (code "170") (name "unconnected-(IC3-(ADC0)PF0-Pad97)") (class "Default")
      (node (ref "IC3") (pin "97") (pinfunction "(ADC0)PF0_97") (pintype "bidirectional"))
    )
    (net (code "171") (name "unconnected-(IC3-(ADC1)PF1-Pad96)") (class "Default")
      (node (ref "IC3") (pin "96") (pinfunction "(ADC1)PF1_96") (pintype "bidirectional"))
    )
    (net (code "172") (name "unconnected-(IC3-(ADC2)PF2-Pad95)") (class "Default")
      (node (ref "IC3") (pin "95") (pinfunction "(ADC2)PF2_95") (pintype "bidirectional"))
    )
    (net (code "173") (name "unconnected-(IC3-(ADC3)PF3-Pad94)") (class "Default")
      (node (ref "IC3") (pin "94") (pinfunction "(ADC3)PF3_94") (pintype "bidirectional"))
    )
    (net (code "174") (name "unconnected-(IC3-(ADC4{slash}TCK)PF4-Pad93)") (class "Default")
      (node (ref "IC3") (pin "93") (pinfunction "(ADC4/TCK)PF4_93") (pintype "bidirectional"))
    )
    (net (code "175") (name "unconnected-(IC3-(ADC5{slash}TMS)PF5-Pad92)") (class "Default")
      (node (ref "IC3") (pin "92") (pinfunction "(ADC5/TMS)PF5_92") (pintype "bidirectional"))
    )
    (net (code "176") (name "unconnected-(IC3-(ADC6{slash}TDO)PF6-Pad91)") (class "Default")
      (node (ref "IC3") (pin "91") (pinfunction "(ADC6/TDO)PF6_91") (pintype "bidirectional"))
    )
    (net (code "177") (name "unconnected-(IC3-(ADC7{slash}TDI)PF7-Pad90)") (class "Default")
      (node (ref "IC3") (pin "90") (pinfunction "(ADC7/TDI)PF7_90") (pintype "bidirectional"))
    )
    (net (code "178") (name "unconnected-(IC3-(ALE)PG2-Pad70)") (class "Default")
      (node (ref "IC3") (pin "70") (pinfunction "(ALE)PG2_70") (pintype "bidirectional"))
    )
    (net (code "179") (name "unconnected-(IC3-(CLKO{slash}ICP3{slash}INT7)PE7-Pad9)") (class "Default")
      (node (ref "IC3") (pin "9") (pinfunction "(CLKO/ICP3/INT7)PE7_9") (pintype "bidirectional"))
    )
    (net (code "180") (name "unconnected-(IC3-(ICP1)PD4-Pad47)") (class "Default")
      (node (ref "IC3") (pin "47") (pinfunction "(ICP1)PD4_47") (pintype "bidirectional"))
    )
    (net (code "181") (name "unconnected-(IC3-(OC0A{slash}OC1C{slash}PCINT7)PB7-Pad26)") (class "Default")
      (node (ref "IC3") (pin "26") (pinfunction "(OC0A/OC1C/PCINT7)PB7_26") (pintype "bidirectional"))
    )
    (net (code "182") (name "unconnected-(IC3-(OC1B{slash}PCINT6)PB6-Pad25)") (class "Default")
      (node (ref "IC3") (pin "25") (pinfunction "(OC1B/PCINT6)PB6_25") (pintype "bidirectional"))
    )
    (net (code "183") (name "unconnected-(IC3-(OC3A{slash}AIN1)PE3-Pad5)") (class "Default")
      (node (ref "IC3") (pin "5") (pinfunction "(OC3A/AIN1)PE3_5") (pintype "bidirectional"))
    )
    (net (code "184") (name "unconnected-(IC3-(OC3C{slash}INT5)PE5-Pad7)") (class "Default")
      (node (ref "IC3") (pin "7") (pinfunction "(OC3C/INT5)PE5_7") (pintype "bidirectional"))
    )
    (net (code "185") (name "unconnected-(IC3-(RD)PG1-Pad52)") (class "Default")
      (node (ref "IC3") (pin "52") (pinfunction "(RD)PG1_52") (pintype "bidirectional"))
    )
    (net (code "186") (name "unconnected-(IC3-(T1)PD6-Pad49)") (class "Default")
      (node (ref "IC3") (pin "49") (pinfunction "(T1)PD6_49") (pintype "bidirectional"))
    )
    (net (code "187") (name "unconnected-(IC3-(T3{slash}INT6)PE6-Pad8)") (class "Default")
      (node (ref "IC3") (pin "8") (pinfunction "(T3/INT6)PE6_8") (pintype "bidirectional"))
    )
    (net (code "188") (name "unconnected-(IC3-(TOSC1)PG4-Pad29)") (class "Default")
      (node (ref "IC3") (pin "29") (pinfunction "(TOSC1)PG4_29") (pintype "bidirectional"))
    )
    (net (code "189") (name "unconnected-(IC3-(TOSC2)PG3-Pad28)") (class "Default")
      (node (ref "IC3") (pin "28") (pinfunction "(TOSC2)PG3_28") (pintype "bidirectional"))
    )
    (net (code "190") (name "unconnected-(IC3-(WR)PG0-Pad51)") (class "Default")
      (node (ref "IC3") (pin "51") (pinfunction "(WR)PG0_51") (pintype "bidirectional"))
    )
    (net (code "191") (name "unconnected-(IC3-(XCK0{slash}AIN0)PE2-Pad4)") (class "Default")
      (node (ref "IC3") (pin "4") (pinfunction "(XCK0/AIN0)PE2_4") (pintype "bidirectional"))
    )
    (net (code "192") (name "unconnected-(IC3-(XCK1)PD5-Pad48)") (class "Default")
      (node (ref "IC3") (pin "48") (pinfunction "(XCK1)PD5_48") (pintype "bidirectional"))
    )
    (net (code "193") (name "unconnected-(IC3-PH2(XCK2)-Pad14)") (class "Default")
      (node (ref "IC3") (pin "14") (pinfunction "PH2(XCK2)_14") (pintype "bidirectional"))
    )
    (net (code "194") (name "unconnected-(IC3-PH4(OC4B)-Pad16)") (class "Default")
      (node (ref "IC3") (pin "16") (pinfunction "PH4(OC4B)_16") (pintype "bidirectional"))
    )
    (net (code "195") (name "unconnected-(IC3-PH7(T4)-Pad27)") (class "Default")
      (node (ref "IC3") (pin "27") (pinfunction "PH7(T4)_27") (pintype "bidirectional"))
    )
    (net (code "196") (name "unconnected-(IC3-PJ2(XCK3{slash}PCINT11)-Pad65)") (class "Default")
      (node (ref "IC3") (pin "65") (pinfunction "PJ2(XCK3/PCINT11)_65") (pintype "bidirectional"))
    )
    (net (code "197") (name "unconnected-(IC3-PJ7-Pad79)") (class "Default")
      (node (ref "IC3") (pin "79") (pinfunction "PJ7_79") (pintype "bidirectional"))
    )
    (net (code "198") (name "unconnected-(IC3-PK0(ADC8{slash}PCINT16)-Pad89)") (class "Default")
      (node (ref "IC3") (pin "89") (pinfunction "PK0(ADC8/PCINT16)_89") (pintype "bidirectional"))
    )
    (net (code "199") (name "unconnected-(IC3-PK1(ADC9{slash}PCINT17)-Pad88)") (class "Default")
      (node (ref "IC3") (pin "88") (pinfunction "PK1(ADC9/PCINT17)_88") (pintype "bidirectional"))
    )
    (net (code "200") (name "unconnected-(IC3-PK2(ADC10{slash}PCINT18)-Pad87)") (class "Default")
      (node (ref "IC3") (pin "87") (pinfunction "PK2(ADC10/PCINT18)_87") (pintype "bidirectional"))
    )
    (net (code "201") (name "unconnected-(IC3-PK3(ADC11{slash}PCINT19)-Pad86)") (class "Default")
      (node (ref "IC3") (pin "86") (pinfunction "PK3(ADC11/PCINT19)_86") (pintype "bidirectional"))
    )
    (net (code "202") (name "unconnected-(IC3-PL0(ICP4)-Pad35)") (class "Default")
      (node (ref "IC3") (pin "35") (pinfunction "PL0(ICP4)_35") (pintype "bidirectional"))
    )
    (net (code "203") (name "unconnected-(IC3-PL1(ICP5)-Pad36)") (class "Default")
      (node (ref "IC3") (pin "36") (pinfunction "PL1(ICP5)_36") (pintype "bidirectional"))
    )
    (net (code "204") (name "unconnected-(IC3-PL2(T5)-Pad37)") (class "Default")
      (node (ref "IC3") (pin "37") (pinfunction "PL2(T5)_37") (pintype "bidirectional"))
    )
    (net (code "205") (name "unconnected-(IC3-PL3(OC5A)-Pad38)") (class "Default")
      (node (ref "IC3") (pin "38") (pinfunction "PL3(OC5A)_38") (pintype "bidirectional"))
    )
    (net (code "206") (name "unconnected-(IC3-PL4(OC5B)-Pad39)") (class "Default")
      (node (ref "IC3") (pin "39") (pinfunction "PL4(OC5B)_39") (pintype "bidirectional"))
    )
    (net (code "207") (name "unconnected-(IC3-PL5(OC5C)-Pad40)") (class "Default")
      (node (ref "IC3") (pin "40") (pinfunction "PL5(OC5C)_40") (pintype "bidirectional"))
    )
    (net (code "208") (name "unconnected-(IC3-PL6-Pad41)") (class "Default")
      (node (ref "IC3") (pin "41") (pinfunction "PL6_41") (pintype "bidirectional"))
    )
    (net (code "209") (name "unconnected-(IC3-PL7-Pad42)") (class "Default")
      (node (ref "IC3") (pin "42") (pinfunction "PL7_42") (pintype "bidirectional"))
    )
    (net (code "210") (name "unconnected-(J1-Pad1)") (class "Default")
      (node (ref "J1") (pin "1") (pinfunction "1_1") (pintype "passive"))
    )
    (net (code "211") (name "unconnected-(J1-Pad4)") (class "Default")
      (node (ref "J1") (pin "4") (pinfunction "4_4") (pintype "passive"))
    )
    (net (code "212") (name "unconnected-(J1-Pad6)") (class "Default")
      (node (ref "J1") (pin "6") (pinfunction "6_6") (pintype "passive"))
    )
    (net (code "213") (name "unconnected-(J1-Pad7)") (class "Default")
      (node (ref "J1") (pin "7") (pinfunction "7_7") (pintype "passive"))
    )
    (net (code "214") (name "unconnected-(J1-Pad8)") (class "Default")
      (node (ref "J1") (pin "8") (pinfunction "8_8") (pintype "passive"))
    )
    (net (code "215") (name "unconnected-(J1-Pad9)") (class "Default")
      (node (ref "J1") (pin "9") (pinfunction "9_9") (pintype "passive"))
    )
    (net (code "216") (name "unconnected-(SD1-DAT1-Pad8)") (class "Default")
      (node (ref "SD1") (pin "8") (pinfunction "DAT1_8") (pintype "bidirectional"))
    )
    (net (code "217") (name "unconnected-(SD1-DAT2-Pad1)") (class "Default")
      (node (ref "SD1") (pin "1") (pinfunction "DAT2_1") (pintype "bidirectional"))
    )
    (net (code "218") (name "unconnected-(U1-R2IN-Pad8)") (class "Default")
      (node (ref "U1") (pin "8") (pinfunction "R2IN_8") (pintype "input"))
    )
    (net (code "219") (name "unconnected-(U1-R2OUT-Pad9)") (class "Default")
      (node (ref "U1") (pin "9") (pinfunction "R2OUT_9") (pintype "output"))
    )
    (net (code "220") (name "unconnected-(U1-T2IN-Pad10)") (class "Default")
      (node (ref "U1") (pin "10") (pinfunction "T2IN_10") (pintype "input"))
    )
    (net (code "221") (name "unconnected-(U1-T2OUT-Pad7)") (class "Default")
      (node (ref "U1") (pin "7") (pinfunction "T2OUT_7") (pintype "output"))
    )
    (net (code "222") (name "unconnected-(U3-AIN2-Pad6)") (class "Default")
      (node (ref "U3") (pin "6") (pinfunction "AIN2_6") (pintype "input"))
    )
    (net (code "223") (name "unconnected-(U3-AIN3-Pad7)") (class "Default")
      (node (ref "U3") (pin "7") (pinfunction "AIN3_7") (pintype "input"))
    )
    (net (code "224") (name "unconnected-(U5-A8-Pad9)") (class "Default")
      (node (ref "U5") (pin "9") (pinfunction "A8_9") (pintype "bidirectional"))
    )
    (net (code "225") (name "unconnected-(U5-B8-Pad11)") (class "Default")
      (node (ref "U5") (pin "11") (pinfunction "B8_11") (pintype "bidirectional"))
    )
    (net (code "226") (name "unconnected-(U6-SQW-Pad7)") (class "Default")
      (node (ref "U6") (pin "7") (pinfunction "SQW_7") (pintype "bidirectional"))
    )
    (net (code "227") (name "unconnected-(WIFI-1.3V-PadJ24)") (class "Default")
      (node (ref "WIFI") (pin "J24") (pinfunction "1.3V_J24") (pintype "passive"))
    )
    (net (code "228") (name "unconnected-(WIFI-GPIO1-PadJ21)") (class "Default")
      (node (ref "WIFI") (pin "J21") (pinfunction "GPIO1_J21") (pintype "bidirectional"))
    )
    (net (code "229") (name "unconnected-(WIFI-RXD-PadJ19)") (class "Default")
      (node (ref "WIFI") (pin "J19") (pinfunction "RXD_J19") (pintype "input"))
    )
    (net (code "230") (name "unconnected-(WIFI-SCL-PadJ2)") (class "Default")
      (node (ref "WIFI") (pin "J2") (pinfunction "SCL_J2") (pintype "bidirectional"))
    )
    (net (code "231") (name "unconnected-(WIFI-SDA-PadJ3)") (class "Default")
      (node (ref "WIFI") (pin "J3") (pinfunction "SDA_J3") (pintype "bidirectional"))
    )
    (net (code "232") (name "unconnected-(WIFI-TXD-PadJ14)") (class "Default")
      (node (ref "WIFI") (pin "J14") (pinfunction "TXD_J14") (pintype "output"))
    )
  )
)
